# Precision_Singleboard_Charlieplex.net
KiCad netlist of a schematic drawn in EAGLE
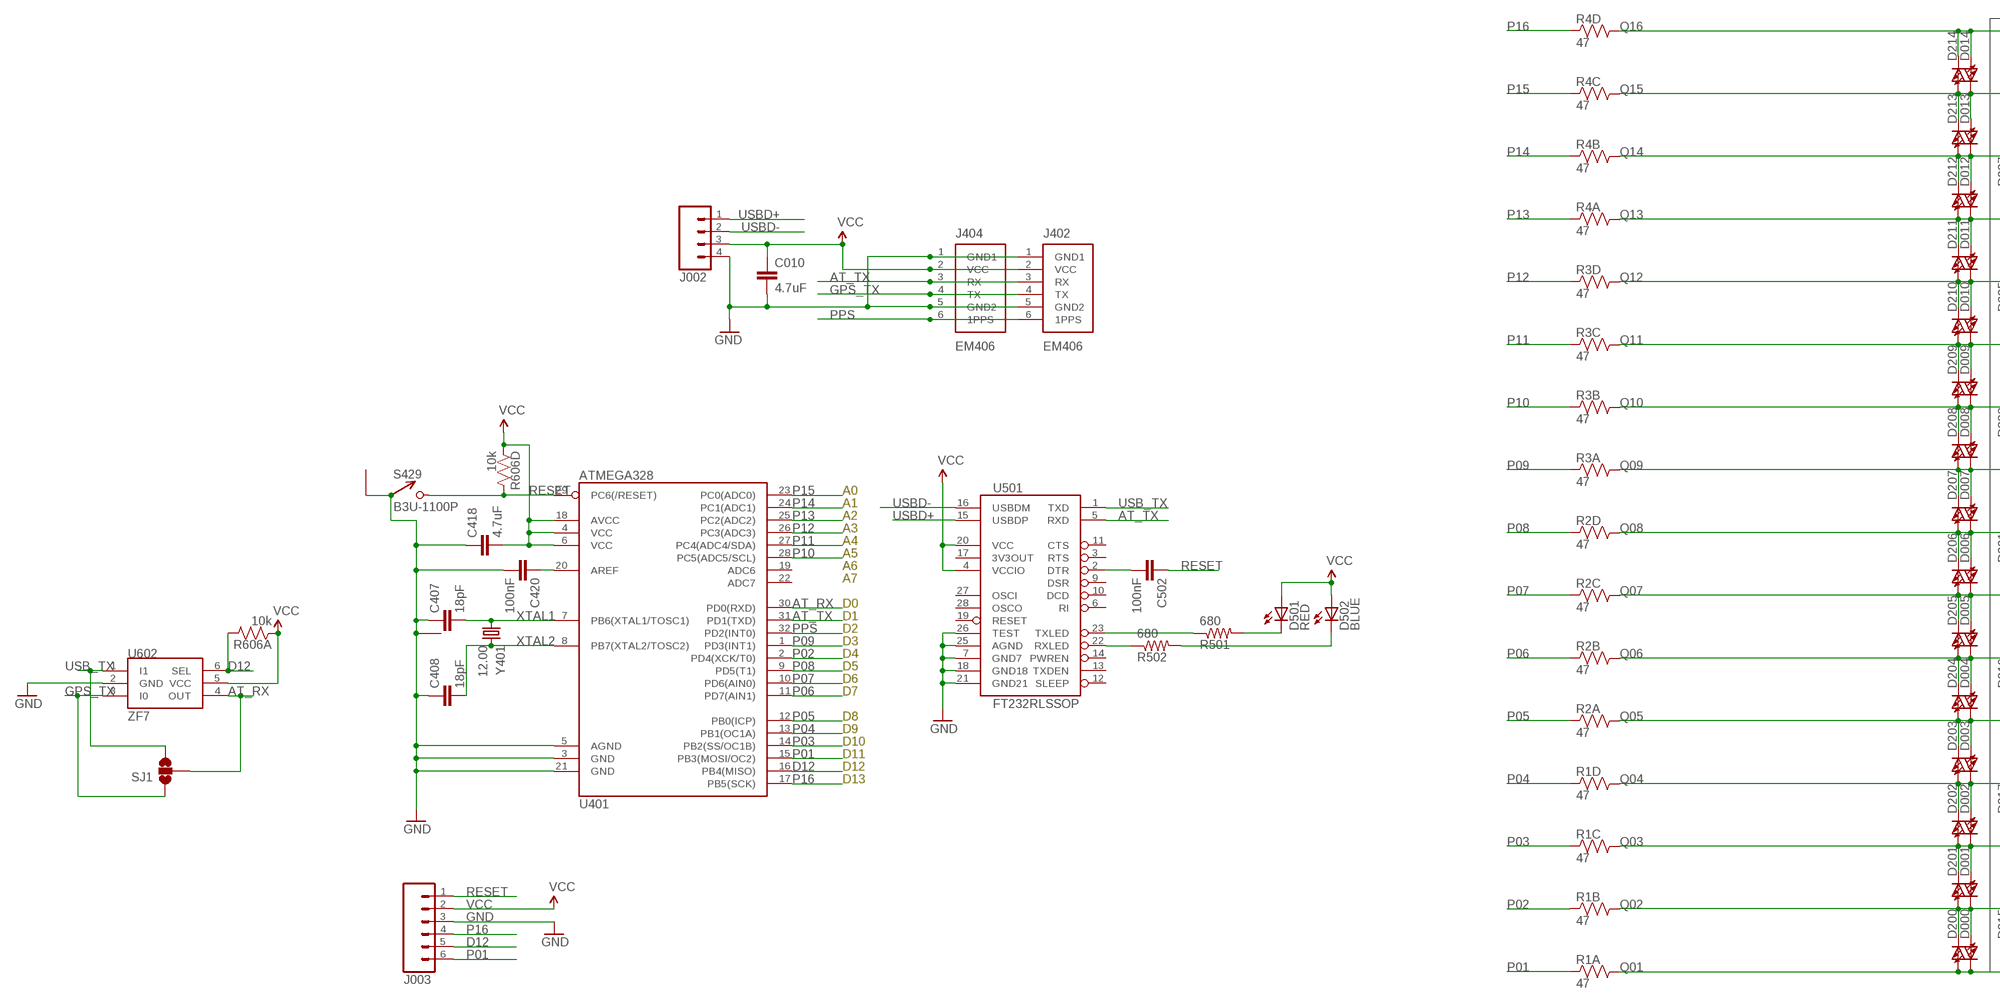
[diagram p0: schematic, sheet 1, part 1 of 2]
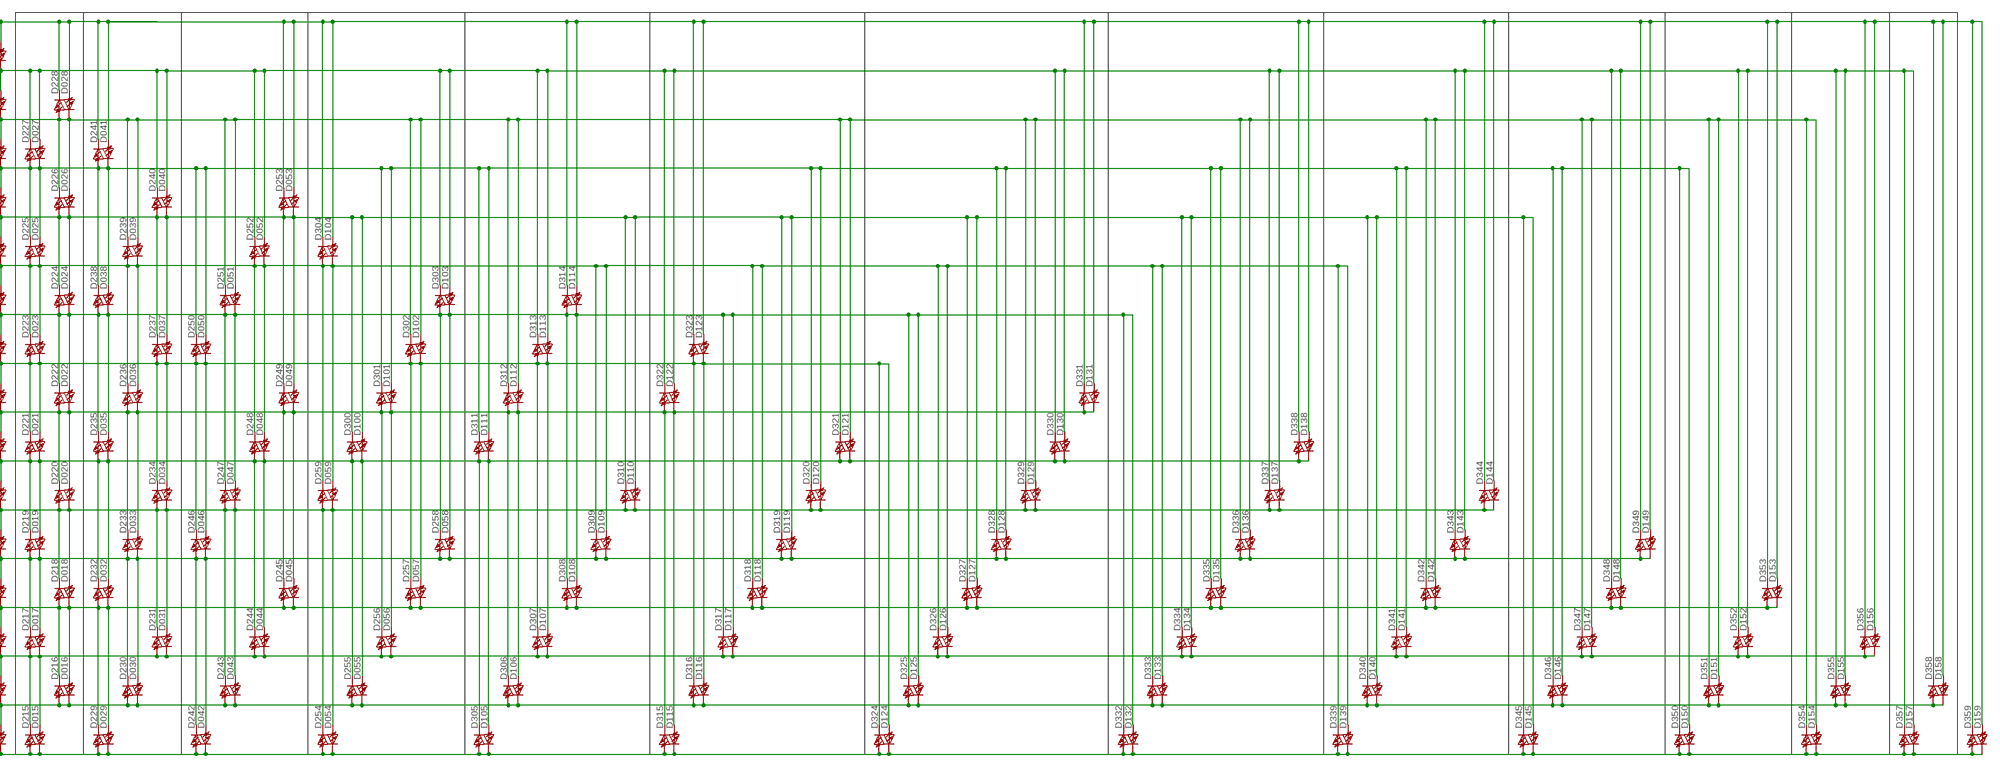
[diagram p1: schematic, sheet 1, part 2 of 2]

(export (version "E")
  (design (tool "Eeschema 10.0.6"))
  (components
    (comp (ref "C010")
      (value "4.7uF")
      (footprint "eagle-import:0603-CAP")
      (libsource (lib "eagle-import") (part "CAP0603-CAP"))
    )
    (comp (ref "C407")
      (value "18pF")
      (footprint "eagle-import:0603-CAP")
      (libsource (lib "eagle-import") (part "CAP0603-CAP"))
    )
    (comp (ref "C408")
      (value "18pF")
      (footprint "eagle-import:0603-CAP")
      (libsource (lib "eagle-import") (part "CAP0603-CAP"))
    )
    (comp (ref "C418")
      (value "4.7uF")
      (footprint "eagle-import:0603-CAP")
      (libsource (lib "eagle-import") (part "CAP0603-CAP"))
    )
    (comp (ref "C420")
      (value "100nF")
      (footprint "eagle-import:0603-CAP")
      (libsource (lib "eagle-import") (part "CAP0603-CAP"))
    )
    (comp (ref "C502")
      (value "100nF")
      (footprint "eagle-import:0603-CAP")
      (libsource (lib "eagle-import") (part "CAP0603-CAP"))
    )
    (comp (ref "D000")
      (value "HOUR")
      (footprint "eagle-import:LED-0603")
      (libsource (lib "eagle-import") (part "LED0603"))
    )
    (comp (ref "D001")
      (value "HOUR")
      (footprint "eagle-import:LED-0603")
      (libsource (lib "eagle-import") (part "LED0603"))
    )
    (comp (ref "D002")
      (value "HOUR")
      (footprint "eagle-import:LED-0603")
      (libsource (lib "eagle-import") (part "LED0603"))
    )
    (comp (ref "D003")
      (value "HOUR")
      (footprint "eagle-import:LED-0603")
      (libsource (lib "eagle-import") (part "LED0603"))
    )
    (comp (ref "D004")
      (value "HOUR")
      (footprint "eagle-import:LED-0603")
      (libsource (lib "eagle-import") (part "LED0603"))
    )
    (comp (ref "D005")
      (value "HOUR")
      (footprint "eagle-import:LED-0603")
      (libsource (lib "eagle-import") (part "LED0603"))
    )
    (comp (ref "D006")
      (value "HOUR")
      (footprint "eagle-import:LED-0603")
      (libsource (lib "eagle-import") (part "LED0603"))
    )
    (comp (ref "D007")
      (value "HOUR")
      (footprint "eagle-import:LED-0603")
      (libsource (lib "eagle-import") (part "LED0603"))
    )
    (comp (ref "D008")
      (value "HOUR")
      (footprint "eagle-import:LED-0603")
      (libsource (lib "eagle-import") (part "LED0603"))
    )
    (comp (ref "D009")
      (value "HOUR")
      (footprint "eagle-import:LED-0603")
      (libsource (lib "eagle-import") (part "LED0603"))
    )
    (comp (ref "D010")
      (value "HOUR")
      (footprint "eagle-import:LED-0603")
      (libsource (lib "eagle-import") (part "LED0603"))
    )
    (comp (ref "D011")
      (value "HOUR")
      (footprint "eagle-import:LED-0603")
      (libsource (lib "eagle-import") (part "LED0603"))
    )
    (comp (ref "D012")
      (value "HOUR")
      (footprint "eagle-import:LED-0603")
      (libsource (lib "eagle-import") (part "LED0603"))
    )
    (comp (ref "D013")
      (value "HOUR")
      (footprint "eagle-import:LED-0603")
      (libsource (lib "eagle-import") (part "LED0603"))
    )
    (comp (ref "D014")
      (value "HOUR")
      (footprint "eagle-import:LED-0603")
      (libsource (lib "eagle-import") (part "LED0603"))
    )
    (comp (ref "D015")
      (value "HOUR")
      (footprint "eagle-import:LED-0603")
      (libsource (lib "eagle-import") (part "LED0603"))
    )
    (comp (ref "D016")
      (value "HOUR")
      (footprint "eagle-import:LED-0603")
      (libsource (lib "eagle-import") (part "LED0603"))
    )
    (comp (ref "D017")
      (value "HOUR")
      (footprint "eagle-import:LED-0603")
      (libsource (lib "eagle-import") (part "LED0603"))
    )
    (comp (ref "D018")
      (value "HOUR")
      (footprint "eagle-import:LED-0603")
      (libsource (lib "eagle-import") (part "LED0603"))
    )
    (comp (ref "D019")
      (value "HOUR")
      (footprint "eagle-import:LED-0603")
      (libsource (lib "eagle-import") (part "LED0603"))
    )
    (comp (ref "D020")
      (value "HOUR")
      (footprint "eagle-import:LED-0603")
      (libsource (lib "eagle-import") (part "LED0603"))
    )
    (comp (ref "D021")
      (value "HOUR")
      (footprint "eagle-import:LED-0603")
      (libsource (lib "eagle-import") (part "LED0603"))
    )
    (comp (ref "D022")
      (value "HOUR")
      (footprint "eagle-import:LED-0603")
      (libsource (lib "eagle-import") (part "LED0603"))
    )
    (comp (ref "D023")
      (value "HOUR")
      (footprint "eagle-import:LED-0603")
      (libsource (lib "eagle-import") (part "LED0603"))
    )
    (comp (ref "D024")
      (value "HOUR")
      (footprint "eagle-import:LED-0603")
      (libsource (lib "eagle-import") (part "LED0603"))
    )
    (comp (ref "D025")
      (value "HOUR")
      (footprint "eagle-import:LED-0603")
      (libsource (lib "eagle-import") (part "LED0603"))
    )
    (comp (ref "D026")
      (value "HOUR")
      (footprint "eagle-import:LED-0603")
      (libsource (lib "eagle-import") (part "LED0603"))
    )
    (comp (ref "D027")
      (value "HOUR")
      (footprint "eagle-import:LED-0603")
      (libsource (lib "eagle-import") (part "LED0603"))
    )
    (comp (ref "D028")
      (value "HOUR")
      (footprint "eagle-import:LED-0603")
      (libsource (lib "eagle-import") (part "LED0603"))
    )
    (comp (ref "D029")
      (value "HOUR")
      (footprint "eagle-import:LED-0603")
      (libsource (lib "eagle-import") (part "LED0603"))
    )
    (comp (ref "D030")
      (value "HOUR")
      (footprint "eagle-import:LED-0603")
      (libsource (lib "eagle-import") (part "LED0603"))
    )
    (comp (ref "D031")
      (value "HOUR")
      (footprint "eagle-import:LED-0603")
      (libsource (lib "eagle-import") (part "LED0603"))
    )
    (comp (ref "D032")
      (value "HOUR")
      (footprint "eagle-import:LED-0603")
      (libsource (lib "eagle-import") (part "LED0603"))
    )
    (comp (ref "D033")
      (value "HOUR")
      (footprint "eagle-import:LED-0603")
      (libsource (lib "eagle-import") (part "LED0603"))
    )
    (comp (ref "D034")
      (value "HOUR")
      (footprint "eagle-import:LED-0603")
      (libsource (lib "eagle-import") (part "LED0603"))
    )
    (comp (ref "D035")
      (value "HOUR")
      (footprint "eagle-import:LED-0603")
      (libsource (lib "eagle-import") (part "LED0603"))
    )
    (comp (ref "D036")
      (value "HOUR")
      (footprint "eagle-import:LED-0603")
      (libsource (lib "eagle-import") (part "LED0603"))
    )
    (comp (ref "D037")
      (value "HOUR")
      (footprint "eagle-import:LED-0603")
      (libsource (lib "eagle-import") (part "LED0603"))
    )
    (comp (ref "D038")
      (value "HOUR")
      (footprint "eagle-import:LED-0603")
      (libsource (lib "eagle-import") (part "LED0603"))
    )
    (comp (ref "D039")
      (value "HOUR")
      (footprint "eagle-import:LED-0603")
      (libsource (lib "eagle-import") (part "LED0603"))
    )
    (comp (ref "D040")
      (value "HOUR")
      (footprint "eagle-import:LED-0603")
      (libsource (lib "eagle-import") (part "LED0603"))
    )
    (comp (ref "D041")
      (value "HOUR")
      (footprint "eagle-import:LED-0603")
      (libsource (lib "eagle-import") (part "LED0603"))
    )
    (comp (ref "D042")
      (value "HOUR")
      (footprint "eagle-import:LED-0603")
      (libsource (lib "eagle-import") (part "LED0603"))
    )
    (comp (ref "D043")
      (value "HOUR")
      (footprint "eagle-import:LED-0603")
      (libsource (lib "eagle-import") (part "LED0603"))
    )
    (comp (ref "D044")
      (value "HOUR")
      (footprint "eagle-import:LED-0603")
      (libsource (lib "eagle-import") (part "LED0603"))
    )
    (comp (ref "D045")
      (value "HOUR")
      (footprint "eagle-import:LED-0603")
      (libsource (lib "eagle-import") (part "LED0603"))
    )
    (comp (ref "D046")
      (value "HOUR")
      (footprint "eagle-import:LED-0603")
      (libsource (lib "eagle-import") (part "LED0603"))
    )
    (comp (ref "D047")
      (value "HOUR")
      (footprint "eagle-import:LED-0603")
      (libsource (lib "eagle-import") (part "LED0603"))
    )
    (comp (ref "D048")
      (value "HOUR")
      (footprint "eagle-import:LED-0603")
      (libsource (lib "eagle-import") (part "LED0603"))
    )
    (comp (ref "D049")
      (value "HOUR")
      (footprint "eagle-import:LED-0603")
      (libsource (lib "eagle-import") (part "LED0603"))
    )
    (comp (ref "D050")
      (value "HOUR")
      (footprint "eagle-import:LED-0603")
      (libsource (lib "eagle-import") (part "LED0603"))
    )
    (comp (ref "D051")
      (value "HOUR")
      (footprint "eagle-import:LED-0603")
      (libsource (lib "eagle-import") (part "LED0603"))
    )
    (comp (ref "D052")
      (value "HOUR")
      (footprint "eagle-import:LED-0603")
      (libsource (lib "eagle-import") (part "LED0603"))
    )
    (comp (ref "D053")
      (value "HOUR")
      (footprint "eagle-import:LED-0603")
      (libsource (lib "eagle-import") (part "LED0603"))
    )
    (comp (ref "D054")
      (value "HOUR")
      (footprint "eagle-import:LED-0603")
      (libsource (lib "eagle-import") (part "LED0603"))
    )
    (comp (ref "D055")
      (value "HOUR")
      (footprint "eagle-import:LED-0603")
      (libsource (lib "eagle-import") (part "LED0603"))
    )
    (comp (ref "D056")
      (value "HOUR")
      (footprint "eagle-import:LED-0603")
      (libsource (lib "eagle-import") (part "LED0603"))
    )
    (comp (ref "D057")
      (value "HOUR")
      (footprint "eagle-import:LED-0603")
      (libsource (lib "eagle-import") (part "LED0603"))
    )
    (comp (ref "D058")
      (value "HOUR")
      (footprint "eagle-import:LED-0603")
      (libsource (lib "eagle-import") (part "LED0603"))
    )
    (comp (ref "D059")
      (value "HOUR")
      (footprint "eagle-import:LED-0603")
      (libsource (lib "eagle-import") (part "LED0603"))
    )
    (comp (ref "D100")
      (value "HOUR")
      (footprint "eagle-import:LED-0603")
      (libsource (lib "eagle-import") (part "LED0603"))
    )
    (comp (ref "D101")
      (value "HOUR")
      (footprint "eagle-import:LED-0603")
      (libsource (lib "eagle-import") (part "LED0603"))
    )
    (comp (ref "D102")
      (value "HOUR")
      (footprint "eagle-import:LED-0603")
      (libsource (lib "eagle-import") (part "LED0603"))
    )
    (comp (ref "D103")
      (value "HOUR")
      (footprint "eagle-import:LED-0603")
      (libsource (lib "eagle-import") (part "LED0603"))
    )
    (comp (ref "D104")
      (value "HOUR")
      (footprint "eagle-import:LED-0603")
      (libsource (lib "eagle-import") (part "LED0603"))
    )
    (comp (ref "D105")
      (value "HOUR")
      (footprint "eagle-import:LED-0603")
      (libsource (lib "eagle-import") (part "LED0603"))
    )
    (comp (ref "D106")
      (value "HOUR")
      (footprint "eagle-import:LED-0603")
      (libsource (lib "eagle-import") (part "LED0603"))
    )
    (comp (ref "D107")
      (value "HOUR")
      (footprint "eagle-import:LED-0603")
      (libsource (lib "eagle-import") (part "LED0603"))
    )
    (comp (ref "D108")
      (value "HOUR")
      (footprint "eagle-import:LED-0603")
      (libsource (lib "eagle-import") (part "LED0603"))
    )
    (comp (ref "D109")
      (value "HOUR")
      (footprint "eagle-import:LED-0603")
      (libsource (lib "eagle-import") (part "LED0603"))
    )
    (comp (ref "D110")
      (value "HOUR")
      (footprint "eagle-import:LED-0603")
      (libsource (lib "eagle-import") (part "LED0603"))
    )
    (comp (ref "D111")
      (value "HOUR")
      (footprint "eagle-import:LED-0603")
      (libsource (lib "eagle-import") (part "LED0603"))
    )
    (comp (ref "D112")
      (value "HOUR")
      (footprint "eagle-import:LED-0603")
      (libsource (lib "eagle-import") (part "LED0603"))
    )
    (comp (ref "D113")
      (value "HOUR")
      (footprint "eagle-import:LED-0603")
      (libsource (lib "eagle-import") (part "LED0603"))
    )
    (comp (ref "D114")
      (value "HOUR")
      (footprint "eagle-import:LED-0603")
      (libsource (lib "eagle-import") (part "LED0603"))
    )
    (comp (ref "D115")
      (value "HOUR")
      (footprint "eagle-import:LED-0603")
      (libsource (lib "eagle-import") (part "LED0603"))
    )
    (comp (ref "D116")
      (value "HOUR")
      (footprint "eagle-import:LED-0603")
      (libsource (lib "eagle-import") (part "LED0603"))
    )
    (comp (ref "D117")
      (value "HOUR")
      (footprint "eagle-import:LED-0603")
      (libsource (lib "eagle-import") (part "LED0603"))
    )
    (comp (ref "D118")
      (value "HOUR")
      (footprint "eagle-import:LED-0603")
      (libsource (lib "eagle-import") (part "LED0603"))
    )
    (comp (ref "D119")
      (value "HOUR")
      (footprint "eagle-import:LED-0603")
      (libsource (lib "eagle-import") (part "LED0603"))
    )
    (comp (ref "D120")
      (value "HOUR")
      (footprint "eagle-import:LED-0603")
      (libsource (lib "eagle-import") (part "LED0603"))
    )
    (comp (ref "D121")
      (value "HOUR")
      (footprint "eagle-import:LED-0603")
      (libsource (lib "eagle-import") (part "LED0603"))
    )
    (comp (ref "D122")
      (value "HOUR")
      (footprint "eagle-import:LED-0603")
      (libsource (lib "eagle-import") (part "LED0603"))
    )
    (comp (ref "D123")
      (value "HOUR")
      (footprint "eagle-import:LED-0603")
      (libsource (lib "eagle-import") (part "LED0603"))
    )
    (comp (ref "D124")
      (value "HOUR")
      (footprint "eagle-import:LED-0603")
      (libsource (lib "eagle-import") (part "LED0603"))
    )
    (comp (ref "D125")
      (value "HOUR")
      (footprint "eagle-import:LED-0603")
      (libsource (lib "eagle-import") (part "LED0603"))
    )
    (comp (ref "D126")
      (value "HOUR")
      (footprint "eagle-import:LED-0603")
      (libsource (lib "eagle-import") (part "LED0603"))
    )
    (comp (ref "D127")
      (value "HOUR")
      (footprint "eagle-import:LED-0603")
      (libsource (lib "eagle-import") (part "LED0603"))
    )
    (comp (ref "D128")
      (value "HOUR")
      (footprint "eagle-import:LED-0603")
      (libsource (lib "eagle-import") (part "LED0603"))
    )
    (comp (ref "D129")
      (value "HOUR")
      (footprint "eagle-import:LED-0603")
      (libsource (lib "eagle-import") (part "LED0603"))
    )
    (comp (ref "D130")
      (value "HOUR")
      (footprint "eagle-import:LED-0603")
      (libsource (lib "eagle-import") (part "LED0603"))
    )
    (comp (ref "D131")
      (value "HOUR")
      (footprint "eagle-import:LED-0603")
      (libsource (lib "eagle-import") (part "LED0603"))
    )
    (comp (ref "D132")
      (value "HOUR")
      (footprint "eagle-import:LED-0603")
      (libsource (lib "eagle-import") (part "LED0603"))
    )
    (comp (ref "D133")
      (value "HOUR")
      (footprint "eagle-import:LED-0603")
      (libsource (lib "eagle-import") (part "LED0603"))
    )
    (comp (ref "D134")
      (value "HOUR")
      (footprint "eagle-import:LED-0603")
      (libsource (lib "eagle-import") (part "LED0603"))
    )
    (comp (ref "D135")
      (value "HOUR")
      (footprint "eagle-import:LED-0603")
      (libsource (lib "eagle-import") (part "LED0603"))
    )
    (comp (ref "D136")
      (value "HOUR")
      (footprint "eagle-import:LED-0603")
      (libsource (lib "eagle-import") (part "LED0603"))
    )
    (comp (ref "D137")
      (value "HOUR")
      (footprint "eagle-import:LED-0603")
      (libsource (lib "eagle-import") (part "LED0603"))
    )
    (comp (ref "D138")
      (value "HOUR")
      (footprint "eagle-import:LED-0603")
      (libsource (lib "eagle-import") (part "LED0603"))
    )
    (comp (ref "D139")
      (value "HOUR")
      (footprint "eagle-import:LED-0603")
      (libsource (lib "eagle-import") (part "LED0603"))
    )
    (comp (ref "D140")
      (value "HOUR")
      (footprint "eagle-import:LED-0603")
      (libsource (lib "eagle-import") (part "LED0603"))
    )
    (comp (ref "D141")
      (value "HOUR")
      (footprint "eagle-import:LED-0603")
      (libsource (lib "eagle-import") (part "LED0603"))
    )
    (comp (ref "D142")
      (value "HOUR")
      (footprint "eagle-import:LED-0603")
      (libsource (lib "eagle-import") (part "LED0603"))
    )
    (comp (ref "D143")
      (value "HOUR")
      (footprint "eagle-import:LED-0603")
      (libsource (lib "eagle-import") (part "LED0603"))
    )
    (comp (ref "D144")
      (value "HOUR")
      (footprint "eagle-import:LED-0603")
      (libsource (lib "eagle-import") (part "LED0603"))
    )
    (comp (ref "D145")
      (value "HOUR")
      (footprint "eagle-import:LED-0603")
      (libsource (lib "eagle-import") (part "LED0603"))
    )
    (comp (ref "D146")
      (value "HOUR")
      (footprint "eagle-import:LED-0603")
      (libsource (lib "eagle-import") (part "LED0603"))
    )
    (comp (ref "D147")
      (value "HOUR")
      (footprint "eagle-import:LED-0603")
      (libsource (lib "eagle-import") (part "LED0603"))
    )
    (comp (ref "D148")
      (value "HOUR")
      (footprint "eagle-import:LED-0603")
      (libsource (lib "eagle-import") (part "LED0603"))
    )
    (comp (ref "D149")
      (value "HOUR")
      (footprint "eagle-import:LED-0603")
      (libsource (lib "eagle-import") (part "LED0603"))
    )
    (comp (ref "D150")
      (value "HOUR")
      (footprint "eagle-import:LED-0603")
      (libsource (lib "eagle-import") (part "LED0603"))
    )
    (comp (ref "D151")
      (value "HOUR")
      (footprint "eagle-import:LED-0603")
      (libsource (lib "eagle-import") (part "LED0603"))
    )
    (comp (ref "D152")
      (value "HOUR")
      (footprint "eagle-import:LED-0603")
      (libsource (lib "eagle-import") (part "LED0603"))
    )
    (comp (ref "D153")
      (value "HOUR")
      (footprint "eagle-import:LED-0603")
      (libsource (lib "eagle-import") (part "LED0603"))
    )
    (comp (ref "D154")
      (value "HOUR")
      (footprint "eagle-import:LED-0603")
      (libsource (lib "eagle-import") (part "LED0603"))
    )
    (comp (ref "D155")
      (value "HOUR")
      (footprint "eagle-import:LED-0603")
      (libsource (lib "eagle-import") (part "LED0603"))
    )
    (comp (ref "D156")
      (value "HOUR")
      (footprint "eagle-import:LED-0603")
      (libsource (lib "eagle-import") (part "LED0603"))
    )
    (comp (ref "D157")
      (value "HOUR")
      (footprint "eagle-import:LED-0603")
      (libsource (lib "eagle-import") (part "LED0603"))
    )
    (comp (ref "D158")
      (value "HOUR")
      (footprint "eagle-import:LED-0603")
      (libsource (lib "eagle-import") (part "LED0603"))
    )
    (comp (ref "D159")
      (value "HOUR")
      (footprint "eagle-import:LED-0603")
      (libsource (lib "eagle-import") (part "LED0603"))
    )
    (comp (ref "D200")
      (value "HOUR")
      (footprint "eagle-import:LED-0603")
      (libsource (lib "eagle-import") (part "LED0603"))
    )
    (comp (ref "D201")
      (value "HOUR")
      (footprint "eagle-import:LED-0603")
      (libsource (lib "eagle-import") (part "LED0603"))
    )
    (comp (ref "D202")
      (value "HOUR")
      (footprint "eagle-import:LED-0603")
      (libsource (lib "eagle-import") (part "LED0603"))
    )
    (comp (ref "D203")
      (value "HOUR")
      (footprint "eagle-import:LED-0603")
      (libsource (lib "eagle-import") (part "LED0603"))
    )
    (comp (ref "D204")
      (value "HOUR")
      (footprint "eagle-import:LED-0603")
      (libsource (lib "eagle-import") (part "LED0603"))
    )
    (comp (ref "D205")
      (value "HOUR")
      (footprint "eagle-import:LED-0603")
      (libsource (lib "eagle-import") (part "LED0603"))
    )
    (comp (ref "D206")
      (value "HOUR")
      (footprint "eagle-import:LED-0603")
      (libsource (lib "eagle-import") (part "LED0603"))
    )
    (comp (ref "D207")
      (value "HOUR")
      (footprint "eagle-import:LED-0603")
      (libsource (lib "eagle-import") (part "LED0603"))
    )
    (comp (ref "D208")
      (value "HOUR")
      (footprint "eagle-import:LED-0603")
      (libsource (lib "eagle-import") (part "LED0603"))
    )
    (comp (ref "D209")
      (value "HOUR")
      (footprint "eagle-import:LED-0603")
      (libsource (lib "eagle-import") (part "LED0603"))
    )
    (comp (ref "D210")
      (value "HOUR")
      (footprint "eagle-import:LED-0603")
      (libsource (lib "eagle-import") (part "LED0603"))
    )
    (comp (ref "D211")
      (value "HOUR")
      (footprint "eagle-import:LED-0603")
      (libsource (lib "eagle-import") (part "LED0603"))
    )
    (comp (ref "D212")
      (value "HOUR")
      (footprint "eagle-import:LED-0603")
      (libsource (lib "eagle-import") (part "LED0603"))
    )
    (comp (ref "D213")
      (value "HOUR")
      (footprint "eagle-import:LED-0603")
      (libsource (lib "eagle-import") (part "LED0603"))
    )
    (comp (ref "D214")
      (value "HOUR")
      (footprint "eagle-import:LED-0603")
      (libsource (lib "eagle-import") (part "LED0603"))
    )
    (comp (ref "D215")
      (value "HOUR")
      (footprint "eagle-import:LED-0603")
      (libsource (lib "eagle-import") (part "LED0603"))
    )
    (comp (ref "D216")
      (value "HOUR")
      (footprint "eagle-import:LED-0603")
      (libsource (lib "eagle-import") (part "LED0603"))
    )
    (comp (ref "D217")
      (value "HOUR")
      (footprint "eagle-import:LED-0603")
      (libsource (lib "eagle-import") (part "LED0603"))
    )
    (comp (ref "D218")
      (value "HOUR")
      (footprint "eagle-import:LED-0603")
      (libsource (lib "eagle-import") (part "LED0603"))
    )
    (comp (ref "D219")
      (value "HOUR")
      (footprint "eagle-import:LED-0603")
      (libsource (lib "eagle-import") (part "LED0603"))
    )
    (comp (ref "D220")
      (value "HOUR")
      (footprint "eagle-import:LED-0603")
      (libsource (lib "eagle-import") (part "LED0603"))
    )
    (comp (ref "D221")
      (value "HOUR")
      (footprint "eagle-import:LED-0603")
      (libsource (lib "eagle-import") (part "LED0603"))
    )
    (comp (ref "D222")
      (value "HOUR")
      (footprint "eagle-import:LED-0603")
      (libsource (lib "eagle-import") (part "LED0603"))
    )
    (comp (ref "D223")
      (value "HOUR")
      (footprint "eagle-import:LED-0603")
      (libsource (lib "eagle-import") (part "LED0603"))
    )
    (comp (ref "D224")
      (value "HOUR")
      (footprint "eagle-import:LED-0603")
      (libsource (lib "eagle-import") (part "LED0603"))
    )
    (comp (ref "D225")
      (value "HOUR")
      (footprint "eagle-import:LED-0603")
      (libsource (lib "eagle-import") (part "LED0603"))
    )
    (comp (ref "D226")
      (value "HOUR")
      (footprint "eagle-import:LED-0603")
      (libsource (lib "eagle-import") (part "LED0603"))
    )
    (comp (ref "D227")
      (value "HOUR")
      (footprint "eagle-import:LED-0603")
      (libsource (lib "eagle-import") (part "LED0603"))
    )
    (comp (ref "D228")
      (value "HOUR")
      (footprint "eagle-import:LED-0603")
      (libsource (lib "eagle-import") (part "LED0603"))
    )
    (comp (ref "D229")
      (value "HOUR")
      (footprint "eagle-import:LED-0603")
      (libsource (lib "eagle-import") (part "LED0603"))
    )
    (comp (ref "D230")
      (value "HOUR")
      (footprint "eagle-import:LED-0603")
      (libsource (lib "eagle-import") (part "LED0603"))
    )
    (comp (ref "D231")
      (value "HOUR")
      (footprint "eagle-import:LED-0603")
      (libsource (lib "eagle-import") (part "LED0603"))
    )
    (comp (ref "D232")
      (value "HOUR")
      (footprint "eagle-import:LED-0603")
      (libsource (lib "eagle-import") (part "LED0603"))
    )
    (comp (ref "D233")
      (value "HOUR")
      (footprint "eagle-import:LED-0603")
      (libsource (lib "eagle-import") (part "LED0603"))
    )
    (comp (ref "D234")
      (value "HOUR")
      (footprint "eagle-import:LED-0603")
      (libsource (lib "eagle-import") (part "LED0603"))
    )
    (comp (ref "D235")
      (value "HOUR")
      (footprint "eagle-import:LED-0603")
      (libsource (lib "eagle-import") (part "LED0603"))
    )
    (comp (ref "D236")
      (value "HOUR")
      (footprint "eagle-import:LED-0603")
      (libsource (lib "eagle-import") (part "LED0603"))
    )
    (comp (ref "D237")
      (value "HOUR")
      (footprint "eagle-import:LED-0603")
      (libsource (lib "eagle-import") (part "LED0603"))
    )
    (comp (ref "D238")
      (value "HOUR")
      (footprint "eagle-import:LED-0603")
      (libsource (lib "eagle-import") (part "LED0603"))
    )
    (comp (ref "D239")
      (value "HOUR")
      (footprint "eagle-import:LED-0603")
      (libsource (lib "eagle-import") (part "LED0603"))
    )
    (comp (ref "D240")
      (value "HOUR")
      (footprint "eagle-import:LED-0603")
      (libsource (lib "eagle-import") (part "LED0603"))
    )
    (comp (ref "D241")
      (value "HOUR")
      (footprint "eagle-import:LED-0603")
      (libsource (lib "eagle-import") (part "LED0603"))
    )
    (comp (ref "D242")
      (value "HOUR")
      (footprint "eagle-import:LED-0603")
      (libsource (lib "eagle-import") (part "LED0603"))
    )
    (comp (ref "D243")
      (value "HOUR")
      (footprint "eagle-import:LED-0603")
      (libsource (lib "eagle-import") (part "LED0603"))
    )
    (comp (ref "D244")
      (value "HOUR")
      (footprint "eagle-import:LED-0603")
      (libsource (lib "eagle-import") (part "LED0603"))
    )
    (comp (ref "D245")
      (value "HOUR")
      (footprint "eagle-import:LED-0603")
      (libsource (lib "eagle-import") (part "LED0603"))
    )
    (comp (ref "D246")
      (value "HOUR")
      (footprint "eagle-import:LED-0603")
      (libsource (lib "eagle-import") (part "LED0603"))
    )
    (comp (ref "D247")
      (value "HOUR")
      (footprint "eagle-import:LED-0603")
      (libsource (lib "eagle-import") (part "LED0603"))
    )
    (comp (ref "D248")
      (value "HOUR")
      (footprint "eagle-import:LED-0603")
      (libsource (lib "eagle-import") (part "LED0603"))
    )
    (comp (ref "D249")
      (value "HOUR")
      (footprint "eagle-import:LED-0603")
      (libsource (lib "eagle-import") (part "LED0603"))
    )
    (comp (ref "D250")
      (value "HOUR")
      (footprint "eagle-import:LED-0603")
      (libsource (lib "eagle-import") (part "LED0603"))
    )
    (comp (ref "D251")
      (value "HOUR")
      (footprint "eagle-import:LED-0603")
      (libsource (lib "eagle-import") (part "LED0603"))
    )
    (comp (ref "D252")
      (value "HOUR")
      (footprint "eagle-import:LED-0603")
      (libsource (lib "eagle-import") (part "LED0603"))
    )
    (comp (ref "D253")
      (value "HOUR")
      (footprint "eagle-import:LED-0603")
      (libsource (lib "eagle-import") (part "LED0603"))
    )
    (comp (ref "D254")
      (value "HOUR")
      (footprint "eagle-import:LED-0603")
      (libsource (lib "eagle-import") (part "LED0603"))
    )
    (comp (ref "D255")
      (value "HOUR")
      (footprint "eagle-import:LED-0603")
      (libsource (lib "eagle-import") (part "LED0603"))
    )
    (comp (ref "D256")
      (value "HOUR")
      (footprint "eagle-import:LED-0603")
      (libsource (lib "eagle-import") (part "LED0603"))
    )
    (comp (ref "D257")
      (value "HOUR")
      (footprint "eagle-import:LED-0603")
      (libsource (lib "eagle-import") (part "LED0603"))
    )
    (comp (ref "D258")
      (value "HOUR")
      (footprint "eagle-import:LED-0603")
      (libsource (lib "eagle-import") (part "LED0603"))
    )
    (comp (ref "D259")
      (value "HOUR")
      (footprint "eagle-import:LED-0603")
      (libsource (lib "eagle-import") (part "LED0603"))
    )
    (comp (ref "D300")
      (value "HOUR")
      (footprint "eagle-import:LED-0603")
      (libsource (lib "eagle-import") (part "LED0603"))
    )
    (comp (ref "D301")
      (value "HOUR")
      (footprint "eagle-import:LED-0603")
      (libsource (lib "eagle-import") (part "LED0603"))
    )
    (comp (ref "D302")
      (value "HOUR")
      (footprint "eagle-import:LED-0603")
      (libsource (lib "eagle-import") (part "LED0603"))
    )
    (comp (ref "D303")
      (value "HOUR")
      (footprint "eagle-import:LED-0603")
      (libsource (lib "eagle-import") (part "LED0603"))
    )
    (comp (ref "D304")
      (value "HOUR")
      (footprint "eagle-import:LED-0603")
      (libsource (lib "eagle-import") (part "LED0603"))
    )
    (comp (ref "D305")
      (value "HOUR")
      (footprint "eagle-import:LED-0603")
      (libsource (lib "eagle-import") (part "LED0603"))
    )
    (comp (ref "D306")
      (value "HOUR")
      (footprint "eagle-import:LED-0603")
      (libsource (lib "eagle-import") (part "LED0603"))
    )
    (comp (ref "D307")
      (value "HOUR")
      (footprint "eagle-import:LED-0603")
      (libsource (lib "eagle-import") (part "LED0603"))
    )
    (comp (ref "D308")
      (value "HOUR")
      (footprint "eagle-import:LED-0603")
      (libsource (lib "eagle-import") (part "LED0603"))
    )
    (comp (ref "D309")
      (value "HOUR")
      (footprint "eagle-import:LED-0603")
      (libsource (lib "eagle-import") (part "LED0603"))
    )
    (comp (ref "D310")
      (value "HOUR")
      (footprint "eagle-import:LED-0603")
      (libsource (lib "eagle-import") (part "LED0603"))
    )
    (comp (ref "D311")
      (value "HOUR")
      (footprint "eagle-import:LED-0603")
      (libsource (lib "eagle-import") (part "LED0603"))
    )
    (comp (ref "D312")
      (value "HOUR")
      (footprint "eagle-import:LED-0603")
      (libsource (lib "eagle-import") (part "LED0603"))
    )
    (comp (ref "D313")
      (value "HOUR")
      (footprint "eagle-import:LED-0603")
      (libsource (lib "eagle-import") (part "LED0603"))
    )
    (comp (ref "D314")
      (value "HOUR")
      (footprint "eagle-import:LED-0603")
      (libsource (lib "eagle-import") (part "LED0603"))
    )
    (comp (ref "D315")
      (value "HOUR")
      (footprint "eagle-import:LED-0603")
      (libsource (lib "eagle-import") (part "LED0603"))
    )
    (comp (ref "D316")
      (value "HOUR")
      (footprint "eagle-import:LED-0603")
      (libsource (lib "eagle-import") (part "LED0603"))
    )
    (comp (ref "D317")
      (value "HOUR")
      (footprint "eagle-import:LED-0603")
      (libsource (lib "eagle-import") (part "LED0603"))
    )
    (comp (ref "D318")
      (value "HOUR")
      (footprint "eagle-import:LED-0603")
      (libsource (lib "eagle-import") (part "LED0603"))
    )
    (comp (ref "D319")
      (value "HOUR")
      (footprint "eagle-import:LED-0603")
      (libsource (lib "eagle-import") (part "LED0603"))
    )
    (comp (ref "D320")
      (value "HOUR")
      (footprint "eagle-import:LED-0603")
      (libsource (lib "eagle-import") (part "LED0603"))
    )
    (comp (ref "D321")
      (value "HOUR")
      (footprint "eagle-import:LED-0603")
      (libsource (lib "eagle-import") (part "LED0603"))
    )
    (comp (ref "D322")
      (value "HOUR")
      (footprint "eagle-import:LED-0603")
      (libsource (lib "eagle-import") (part "LED0603"))
    )
    (comp (ref "D323")
      (value "HOUR")
      (footprint "eagle-import:LED-0603")
      (libsource (lib "eagle-import") (part "LED0603"))
    )
    (comp (ref "D324")
      (value "HOUR")
      (footprint "eagle-import:LED-0603")
      (libsource (lib "eagle-import") (part "LED0603"))
    )
    (comp (ref "D325")
      (value "HOUR")
      (footprint "eagle-import:LED-0603")
      (libsource (lib "eagle-import") (part "LED0603"))
    )
    (comp (ref "D326")
      (value "HOUR")
      (footprint "eagle-import:LED-0603")
      (libsource (lib "eagle-import") (part "LED0603"))
    )
    (comp (ref "D327")
      (value "HOUR")
      (footprint "eagle-import:LED-0603")
      (libsource (lib "eagle-import") (part "LED0603"))
    )
    (comp (ref "D328")
      (value "HOUR")
      (footprint "eagle-import:LED-0603")
      (libsource (lib "eagle-import") (part "LED0603"))
    )
    (comp (ref "D329")
      (value "HOUR")
      (footprint "eagle-import:LED-0603")
      (libsource (lib "eagle-import") (part "LED0603"))
    )
    (comp (ref "D330")
      (value "HOUR")
      (footprint "eagle-import:LED-0603")
      (libsource (lib "eagle-import") (part "LED0603"))
    )
    (comp (ref "D331")
      (value "HOUR")
      (footprint "eagle-import:LED-0603")
      (libsource (lib "eagle-import") (part "LED0603"))
    )
    (comp (ref "D332")
      (value "HOUR")
      (footprint "eagle-import:LED-0603")
      (libsource (lib "eagle-import") (part "LED0603"))
    )
    (comp (ref "D333")
      (value "HOUR")
      (footprint "eagle-import:LED-0603")
      (libsource (lib "eagle-import") (part "LED0603"))
    )
    (comp (ref "D334")
      (value "HOUR")
      (footprint "eagle-import:LED-0603")
      (libsource (lib "eagle-import") (part "LED0603"))
    )
    (comp (ref "D335")
      (value "HOUR")
      (footprint "eagle-import:LED-0603")
      (libsource (lib "eagle-import") (part "LED0603"))
    )
    (comp (ref "D336")
      (value "HOUR")
      (footprint "eagle-import:LED-0603")
      (libsource (lib "eagle-import") (part "LED0603"))
    )
    (comp (ref "D337")
      (value "HOUR")
      (footprint "eagle-import:LED-0603")
      (libsource (lib "eagle-import") (part "LED0603"))
    )
    (comp (ref "D338")
      (value "HOUR")
      (footprint "eagle-import:LED-0603")
      (libsource (lib "eagle-import") (part "LED0603"))
    )
    (comp (ref "D339")
      (value "HOUR")
      (footprint "eagle-import:LED-0603")
      (libsource (lib "eagle-import") (part "LED0603"))
    )
    (comp (ref "D340")
      (value "HOUR")
      (footprint "eagle-import:LED-0603")
      (libsource (lib "eagle-import") (part "LED0603"))
    )
    (comp (ref "D341")
      (value "HOUR")
      (footprint "eagle-import:LED-0603")
      (libsource (lib "eagle-import") (part "LED0603"))
    )
    (comp (ref "D342")
      (value "HOUR")
      (footprint "eagle-import:LED-0603")
      (libsource (lib "eagle-import") (part "LED0603"))
    )
    (comp (ref "D343")
      (value "HOUR")
      (footprint "eagle-import:LED-0603")
      (libsource (lib "eagle-import") (part "LED0603"))
    )
    (comp (ref "D344")
      (value "HOUR")
      (footprint "eagle-import:LED-0603")
      (libsource (lib "eagle-import") (part "LED0603"))
    )
    (comp (ref "D345")
      (value "HOUR")
      (footprint "eagle-import:LED-0603")
      (libsource (lib "eagle-import") (part "LED0603"))
    )
    (comp (ref "D346")
      (value "HOUR")
      (footprint "eagle-import:LED-0603")
      (libsource (lib "eagle-import") (part "LED0603"))
    )
    (comp (ref "D347")
      (value "HOUR")
      (footprint "eagle-import:LED-0603")
      (libsource (lib "eagle-import") (part "LED0603"))
    )
    (comp (ref "D348")
      (value "HOUR")
      (footprint "eagle-import:LED-0603")
      (libsource (lib "eagle-import") (part "LED0603"))
    )
    (comp (ref "D349")
      (value "HOUR")
      (footprint "eagle-import:LED-0603")
      (libsource (lib "eagle-import") (part "LED0603"))
    )
    (comp (ref "D350")
      (value "HOUR")
      (footprint "eagle-import:LED-0603")
      (libsource (lib "eagle-import") (part "LED0603"))
    )
    (comp (ref "D351")
      (value "HOUR")
      (footprint "eagle-import:LED-0603")
      (libsource (lib "eagle-import") (part "LED0603"))
    )
    (comp (ref "D352")
      (value "HOUR")
      (footprint "eagle-import:LED-0603")
      (libsource (lib "eagle-import") (part "LED0603"))
    )
    (comp (ref "D353")
      (value "HOUR")
      (footprint "eagle-import:LED-0603")
      (libsource (lib "eagle-import") (part "LED0603"))
    )
    (comp (ref "D354")
      (value "HOUR")
      (footprint "eagle-import:LED-0603")
      (libsource (lib "eagle-import") (part "LED0603"))
    )
    (comp (ref "D355")
      (value "HOUR")
      (footprint "eagle-import:LED-0603")
      (libsource (lib "eagle-import") (part "LED0603"))
    )
    (comp (ref "D356")
      (value "HOUR")
      (footprint "eagle-import:LED-0603")
      (libsource (lib "eagle-import") (part "LED0603"))
    )
    (comp (ref "D357")
      (value "HOUR")
      (footprint "eagle-import:LED-0603")
      (libsource (lib "eagle-import") (part "LED0603"))
    )
    (comp (ref "D358")
      (value "HOUR")
      (footprint "eagle-import:LED-0603")
      (libsource (lib "eagle-import") (part "LED0603"))
    )
    (comp (ref "D359")
      (value "HOUR")
      (footprint "eagle-import:LED-0603")
      (libsource (lib "eagle-import") (part "LED0603"))
    )
    (comp (ref "D501")
      (value "RED")
      (footprint "eagle-import:LED-0603")
      (libsource (lib "eagle-import") (part "LED0603"))
    )
    (comp (ref "D502")
      (value "BLUE")
      (footprint "eagle-import:LED-0603")
      (libsource (lib "eagle-import") (part "LED0603"))
    )
    (comp (ref "J002")
      (value "M04PTH")
      (footprint "eagle-import:1X04")
      (libsource (lib "eagle-import") (part "M04PTH"))
    )
    (comp (ref "J003")
      (value "M06SIP")
      (footprint "eagle-import:1X06")
      (libsource (lib "eagle-import") (part "M06SIP"))
    )
    (comp (ref "J402")
      (value "EM406")
      (footprint "eagle-import:EM406")
      (libsource (lib "eagle-import") (part "EM406"))
    )
    (comp (ref "J404")
      (value "EM406")
      (footprint "eagle-import:EM406")
      (libsource (lib "eagle-import") (part "EM406"))
    )
    (comp (ref "R1")
      (value "47")
      (footprint "eagle-import:CRA04")
      (libsource (lib "eagle-import") (part "RP404"))
    )
    (comp (ref "R2")
      (value "47")
      (footprint "eagle-import:CRA04")
      (libsource (lib "eagle-import") (part "RP404"))
    )
    (comp (ref "R3")
      (value "47")
      (footprint "eagle-import:CRA04")
      (libsource (lib "eagle-import") (part "RP404"))
    )
    (comp (ref "R4")
      (value "47")
      (footprint "eagle-import:CRA04")
      (libsource (lib "eagle-import") (part "RP404"))
    )
    (comp (ref "R501")
      (value "680")
      (footprint "eagle-import:0603-RES")
      (libsource (lib "eagle-import") (part "RESISTOR0603-RES"))
    )
    (comp (ref "R502")
      (value "680")
      (footprint "eagle-import:0603-RES")
      (libsource (lib "eagle-import") (part "RESISTOR0603-RES"))
    )
    (comp (ref "R606")
      (value "10k")
      (footprint "eagle-import:CRA04")
      (libsource (lib "eagle-import") (part "RP404"))
    )
    (comp (ref "S429")
      (value "B3U-1100P")
      (footprint "eagle-import:B3U-1100P")
      (libsource (lib "eagle-import") (part "B3U-1100P"))
    )
    (comp (ref "SJ1")
      (value "SOLDERJUMPER_2WAYS")
      (footprint "eagle-import:SJ_3")
      (libsource (lib "eagle-import") (part "SOLDERJUMPER_2WAYS"))
    )
    (comp (ref "U401")
      (value "ATMEGA328")
      (footprint "eagle-import:TQFP32-08")
      (libsource (lib "eagle-import") (part "ATMEGA168"))
    )
    (comp (ref "U501")
      (value "FT232RLSSOP")
      (footprint "eagle-import:SSOP28DB")
      (libsource (lib "eagle-import") (part "FT232RLSSOP"))
    )
    (comp (ref "U602")
      (value "ZF7")
      (footprint "eagle-import:SC-70-6")
      (libsource (lib "eagle-import") (part "NC7SZ157"))
    )
    (comp (ref "Y401")
      (value "12.00")
      (footprint "eagle-import:CRYSTAL_SMD")
      (libsource (lib "eagle-import") (part "TSX-3225"))
    )
  )
  (nets
    (net (code "1") (name "/AT_RX") (class "Default")
      (node (ref "SJ1") (pin "2") (pinfunction "2_2") (pintype "passive"))
      (node (ref "U401") (pin "30") (pinfunction "PD0(RXD)_30") (pintype "bidirectional"))
      (node (ref "U602") (pin "4") (pinfunction "OUT_4") (pintype "bidirectional"))
    )
    (net (code "2") (name "/AT_TX") (class "Default")
      (node (ref "J402") (pin "3") (pinfunction "RX_3") (pintype "bidirectional"))
      (node (ref "J404") (pin "3") (pinfunction "RX_3") (pintype "bidirectional"))
      (node (ref "U401") (pin "31") (pinfunction "PD1(TXD)_31") (pintype "bidirectional"))
      (node (ref "U501") (pin "5") (pinfunction "RXD_5") (pintype "input"))
    )
    (net (code "3") (name "/D12") (class "Default")
      (node (ref "J003") (pin "5") (pinfunction "5_5") (pintype "passive"))
      (node (ref "R606") (pin "8") (pinfunction "2_8") (pintype "passive"))
      (node (ref "U401") (pin "16") (pinfunction "PB4(MISO)_16") (pintype "bidirectional"))
      (node (ref "U602") (pin "6") (pinfunction "SEL_6") (pintype "bidirectional"))
    )
    (net (code "4") (name "/GPS_TX") (class "Default")
      (node (ref "J402") (pin "4") (pinfunction "TX_4") (pintype "bidirectional"))
      (node (ref "J404") (pin "4") (pinfunction "TX_4") (pintype "bidirectional"))
      (node (ref "SJ1") (pin "1") (pinfunction "1_1") (pintype "passive"))
      (node (ref "U602") (pin "3") (pinfunction "I0_3") (pintype "bidirectional"))
    )
    (net (code "5") (name "/P01") (class "Default")
      (node (ref "J003") (pin "6") (pinfunction "6_6") (pintype "passive"))
      (node (ref "R1") (pin "1") (pinfunction "1_1") (pintype "passive"))
      (node (ref "U401") (pin "15") (pinfunction "PB3(MOSI/OC2)_15") (pintype "bidirectional"))
    )
    (net (code "6") (name "/P02") (class "Default")
      (node (ref "R1") (pin "2") (pinfunction "1_2") (pintype "passive"))
      (node (ref "U401") (pin "2") (pinfunction "PD4(XCK/T0)_2") (pintype "bidirectional"))
    )
    (net (code "7") (name "/P03") (class "Default")
      (node (ref "R1") (pin "3") (pinfunction "1_3") (pintype "passive"))
      (node (ref "U401") (pin "14") (pinfunction "PB2(SS/OC1B)_14") (pintype "bidirectional"))
    )
    (net (code "8") (name "/P04") (class "Default")
      (node (ref "R1") (pin "4") (pinfunction "1_4") (pintype "passive"))
      (node (ref "U401") (pin "13") (pinfunction "PB1(OC1A)_13") (pintype "bidirectional"))
    )
    (net (code "9") (name "/P05") (class "Default")
      (node (ref "R2") (pin "1") (pinfunction "1_1") (pintype "passive"))
      (node (ref "U401") (pin "12") (pinfunction "PB0(ICP)_12") (pintype "bidirectional"))
    )
    (net (code "10") (name "/P06") (class "Default")
      (node (ref "R2") (pin "2") (pinfunction "1_2") (pintype "passive"))
      (node (ref "U401") (pin "11") (pinfunction "PD7(AIN1)_11") (pintype "bidirectional"))
    )
    (net (code "11") (name "/P07") (class "Default")
      (node (ref "R2") (pin "3") (pinfunction "1_3") (pintype "passive"))
      (node (ref "U401") (pin "10") (pinfunction "PD6(AIN0)_10") (pintype "bidirectional"))
    )
    (net (code "12") (name "/P08") (class "Default")
      (node (ref "R2") (pin "4") (pinfunction "1_4") (pintype "passive"))
      (node (ref "U401") (pin "9") (pinfunction "PD5(T1)_9") (pintype "bidirectional"))
    )
    (net (code "13") (name "/P09") (class "Default")
      (node (ref "R3") (pin "1") (pinfunction "1_1") (pintype "passive"))
      (node (ref "U401") (pin "1") (pinfunction "PD3(INT1)_1") (pintype "bidirectional"))
    )
    (net (code "14") (name "/P10") (class "Default")
      (node (ref "R3") (pin "2") (pinfunction "1_2") (pintype "passive"))
      (node (ref "U401") (pin "28") (pinfunction "PC5(ADC5/SCL)_28") (pintype "bidirectional"))
    )
    (net (code "15") (name "/P11") (class "Default")
      (node (ref "R3") (pin "3") (pinfunction "1_3") (pintype "passive"))
      (node (ref "U401") (pin "27") (pinfunction "PC4(ADC4/SDA)_27") (pintype "bidirectional"))
    )
    (net (code "16") (name "/P12") (class "Default")
      (node (ref "R3") (pin "4") (pinfunction "1_4") (pintype "passive"))
      (node (ref "U401") (pin "26") (pinfunction "PC3(ADC3)_26") (pintype "bidirectional"))
    )
    (net (code "17") (name "/P13") (class "Default")
      (node (ref "R4") (pin "1") (pinfunction "1_1") (pintype "passive"))
      (node (ref "U401") (pin "25") (pinfunction "PC2(ADC2)_25") (pintype "bidirectional"))
    )
    (net (code "18") (name "/P14") (class "Default")
      (node (ref "R4") (pin "2") (pinfunction "1_2") (pintype "passive"))
      (node (ref "U401") (pin "24") (pinfunction "PC1(ADC1)_24") (pintype "bidirectional"))
    )
    (net (code "19") (name "/P15") (class "Default")
      (node (ref "R4") (pin "3") (pinfunction "1_3") (pintype "passive"))
      (node (ref "U401") (pin "23") (pinfunction "PC0(ADC0)_23") (pintype "bidirectional"))
    )
    (net (code "20") (name "/P16") (class "Default")
      (node (ref "J003") (pin "4") (pinfunction "4_4") (pintype "passive"))
      (node (ref "R4") (pin "4") (pinfunction "1_4") (pintype "passive"))
      (node (ref "U401") (pin "17") (pinfunction "PB5(SCK)_17") (pintype "bidirectional"))
    )
    (net (code "21") (name "/PPS") (class "Default")
      (node (ref "J402") (pin "6") (pinfunction "1PPS_6") (pintype "bidirectional"))
      (node (ref "J404") (pin "6") (pinfunction "1PPS_6") (pintype "bidirectional"))
      (node (ref "U401") (pin "32") (pinfunction "PD2(INT0)_32") (pintype "bidirectional"))
    )
    (net (code "22") (name "/Q01") (class "Default")
      (node (ref "D000") (pin "C") (pinfunction "C_C") (pintype "passive"))
      (node (ref "D015") (pin "C") (pinfunction "C_C") (pintype "passive"))
      (node (ref "D029") (pin "C") (pinfunction "C_C") (pintype "passive"))
      (node (ref "D042") (pin "C") (pinfunction "C_C") (pintype "passive"))
      (node (ref "D054") (pin "C") (pinfunction "C_C") (pintype "passive"))
      (node (ref "D105") (pin "C") (pinfunction "C_C") (pintype "passive"))
      (node (ref "D115") (pin "C") (pinfunction "C_C") (pintype "passive"))
      (node (ref "D124") (pin "C") (pinfunction "C_C") (pintype "passive"))
      (node (ref "D132") (pin "C") (pinfunction "C_C") (pintype "passive"))
      (node (ref "D139") (pin "C") (pinfunction "C_C") (pintype "passive"))
      (node (ref "D145") (pin "C") (pinfunction "C_C") (pintype "passive"))
      (node (ref "D150") (pin "C") (pinfunction "C_C") (pintype "passive"))
      (node (ref "D154") (pin "C") (pinfunction "C_C") (pintype "passive"))
      (node (ref "D157") (pin "C") (pinfunction "C_C") (pintype "passive"))
      (node (ref "D159") (pin "C") (pinfunction "C_C") (pintype "passive"))
      (node (ref "D200") (pin "A") (pinfunction "A_A") (pintype "passive"))
      (node (ref "D215") (pin "A") (pinfunction "A_A") (pintype "passive"))
      (node (ref "D229") (pin "A") (pinfunction "A_A") (pintype "passive"))
      (node (ref "D242") (pin "A") (pinfunction "A_A") (pintype "passive"))
      (node (ref "D254") (pin "A") (pinfunction "A_A") (pintype "passive"))
      (node (ref "D305") (pin "A") (pinfunction "A_A") (pintype "passive"))
      (node (ref "D315") (pin "A") (pinfunction "A_A") (pintype "passive"))
      (node (ref "D324") (pin "A") (pinfunction "A_A") (pintype "passive"))
      (node (ref "D332") (pin "A") (pinfunction "A_A") (pintype "passive"))
      (node (ref "D339") (pin "A") (pinfunction "A_A") (pintype "passive"))
      (node (ref "D345") (pin "A") (pinfunction "A_A") (pintype "passive"))
      (node (ref "D350") (pin "A") (pinfunction "A_A") (pintype "passive"))
      (node (ref "D354") (pin "A") (pinfunction "A_A") (pintype "passive"))
      (node (ref "D357") (pin "A") (pinfunction "A_A") (pintype "passive"))
      (node (ref "D359") (pin "A") (pinfunction "A_A") (pintype "passive"))
      (node (ref "R1") (pin "8") (pinfunction "2_8") (pintype "passive"))
    )
    (net (code "23") (name "/Q02") (class "Default")
      (node (ref "D000") (pin "A") (pinfunction "A_A") (pintype "passive"))
      (node (ref "D001") (pin "C") (pinfunction "C_C") (pintype "passive"))
      (node (ref "D016") (pin "C") (pinfunction "C_C") (pintype "passive"))
      (node (ref "D030") (pin "C") (pinfunction "C_C") (pintype "passive"))
      (node (ref "D043") (pin "C") (pinfunction "C_C") (pintype "passive"))
      (node (ref "D055") (pin "C") (pinfunction "C_C") (pintype "passive"))
      (node (ref "D106") (pin "C") (pinfunction "C_C") (pintype "passive"))
      (node (ref "D116") (pin "C") (pinfunction "C_C") (pintype "passive"))
      (node (ref "D125") (pin "C") (pinfunction "C_C") (pintype "passive"))
      (node (ref "D133") (pin "C") (pinfunction "C_C") (pintype "passive"))
      (node (ref "D140") (pin "C") (pinfunction "C_C") (pintype "passive"))
      (node (ref "D146") (pin "C") (pinfunction "C_C") (pintype "passive"))
      (node (ref "D151") (pin "C") (pinfunction "C_C") (pintype "passive"))
      (node (ref "D155") (pin "C") (pinfunction "C_C") (pintype "passive"))
      (node (ref "D158") (pin "C") (pinfunction "C_C") (pintype "passive"))
      (node (ref "D200") (pin "C") (pinfunction "C_C") (pintype "passive"))
      (node (ref "D201") (pin "A") (pinfunction "A_A") (pintype "passive"))
      (node (ref "D216") (pin "A") (pinfunction "A_A") (pintype "passive"))
      (node (ref "D230") (pin "A") (pinfunction "A_A") (pintype "passive"))
      (node (ref "D243") (pin "A") (pinfunction "A_A") (pintype "passive"))
      (node (ref "D255") (pin "A") (pinfunction "A_A") (pintype "passive"))
      (node (ref "D306") (pin "A") (pinfunction "A_A") (pintype "passive"))
      (node (ref "D316") (pin "A") (pinfunction "A_A") (pintype "passive"))
      (node (ref "D325") (pin "A") (pinfunction "A_A") (pintype "passive"))
      (node (ref "D333") (pin "A") (pinfunction "A_A") (pintype "passive"))
      (node (ref "D340") (pin "A") (pinfunction "A_A") (pintype "passive"))
      (node (ref "D346") (pin "A") (pinfunction "A_A") (pintype "passive"))
      (node (ref "D351") (pin "A") (pinfunction "A_A") (pintype "passive"))
      (node (ref "D355") (pin "A") (pinfunction "A_A") (pintype "passive"))
      (node (ref "D358") (pin "A") (pinfunction "A_A") (pintype "passive"))
      (node (ref "R1") (pin "7") (pinfunction "2_7") (pintype "passive"))
    )
    (net (code "24") (name "/Q03") (class "Default")
      (node (ref "D001") (pin "A") (pinfunction "A_A") (pintype "passive"))
      (node (ref "D002") (pin "C") (pinfunction "C_C") (pintype "passive"))
      (node (ref "D015") (pin "A") (pinfunction "A_A") (pintype "passive"))
      (node (ref "D017") (pin "C") (pinfunction "C_C") (pintype "passive"))
      (node (ref "D031") (pin "C") (pinfunction "C_C") (pintype "passive"))
      (node (ref "D044") (pin "C") (pinfunction "C_C") (pintype "passive"))
      (node (ref "D056") (pin "C") (pinfunction "C_C") (pintype "passive"))
      (node (ref "D107") (pin "C") (pinfunction "C_C") (pintype "passive"))
      (node (ref "D117") (pin "C") (pinfunction "C_C") (pintype "passive"))
      (node (ref "D126") (pin "C") (pinfunction "C_C") (pintype "passive"))
      (node (ref "D134") (pin "C") (pinfunction "C_C") (pintype "passive"))
      (node (ref "D141") (pin "C") (pinfunction "C_C") (pintype "passive"))
      (node (ref "D147") (pin "C") (pinfunction "C_C") (pintype "passive"))
      (node (ref "D152") (pin "C") (pinfunction "C_C") (pintype "passive"))
      (node (ref "D156") (pin "C") (pinfunction "C_C") (pintype "passive"))
      (node (ref "D201") (pin "C") (pinfunction "C_C") (pintype "passive"))
      (node (ref "D202") (pin "A") (pinfunction "A_A") (pintype "passive"))
      (node (ref "D215") (pin "C") (pinfunction "C_C") (pintype "passive"))
      (node (ref "D217") (pin "A") (pinfunction "A_A") (pintype "passive"))
      (node (ref "D231") (pin "A") (pinfunction "A_A") (pintype "passive"))
      (node (ref "D244") (pin "A") (pinfunction "A_A") (pintype "passive"))
      (node (ref "D256") (pin "A") (pinfunction "A_A") (pintype "passive"))
      (node (ref "D307") (pin "A") (pinfunction "A_A") (pintype "passive"))
      (node (ref "D317") (pin "A") (pinfunction "A_A") (pintype "passive"))
      (node (ref "D326") (pin "A") (pinfunction "A_A") (pintype "passive"))
      (node (ref "D334") (pin "A") (pinfunction "A_A") (pintype "passive"))
      (node (ref "D341") (pin "A") (pinfunction "A_A") (pintype "passive"))
      (node (ref "D347") (pin "A") (pinfunction "A_A") (pintype "passive"))
      (node (ref "D352") (pin "A") (pinfunction "A_A") (pintype "passive"))
      (node (ref "D356") (pin "A") (pinfunction "A_A") (pintype "passive"))
      (node (ref "R1") (pin "6") (pinfunction "2_6") (pintype "passive"))
    )
    (net (code "25") (name "/Q04") (class "Default")
      (node (ref "D002") (pin "A") (pinfunction "A_A") (pintype "passive"))
      (node (ref "D003") (pin "C") (pinfunction "C_C") (pintype "passive"))
      (node (ref "D016") (pin "A") (pinfunction "A_A") (pintype "passive"))
      (node (ref "D018") (pin "C") (pinfunction "C_C") (pintype "passive"))
      (node (ref "D029") (pin "A") (pinfunction "A_A") (pintype "passive"))
      (node (ref "D032") (pin "C") (pinfunction "C_C") (pintype "passive"))
      (node (ref "D045") (pin "C") (pinfunction "C_C") (pintype "passive"))
      (node (ref "D057") (pin "C") (pinfunction "C_C") (pintype "passive"))
      (node (ref "D108") (pin "C") (pinfunction "C_C") (pintype "passive"))
      (node (ref "D118") (pin "C") (pinfunction "C_C") (pintype "passive"))
      (node (ref "D127") (pin "C") (pinfunction "C_C") (pintype "passive"))
      (node (ref "D135") (pin "C") (pinfunction "C_C") (pintype "passive"))
      (node (ref "D142") (pin "C") (pinfunction "C_C") (pintype "passive"))
      (node (ref "D148") (pin "C") (pinfunction "C_C") (pintype "passive"))
      (node (ref "D153") (pin "C") (pinfunction "C_C") (pintype "passive"))
      (node (ref "D202") (pin "C") (pinfunction "C_C") (pintype "passive"))
      (node (ref "D203") (pin "A") (pinfunction "A_A") (pintype "passive"))
      (node (ref "D216") (pin "C") (pinfunction "C_C") (pintype "passive"))
      (node (ref "D218") (pin "A") (pinfunction "A_A") (pintype "passive"))
      (node (ref "D229") (pin "C") (pinfunction "C_C") (pintype "passive"))
      (node (ref "D232") (pin "A") (pinfunction "A_A") (pintype "passive"))
      (node (ref "D245") (pin "A") (pinfunction "A_A") (pintype "passive"))
      (node (ref "D257") (pin "A") (pinfunction "A_A") (pintype "passive"))
      (node (ref "D308") (pin "A") (pinfunction "A_A") (pintype "passive"))
      (node (ref "D318") (pin "A") (pinfunction "A_A") (pintype "passive"))
      (node (ref "D327") (pin "A") (pinfunction "A_A") (pintype "passive"))
      (node (ref "D335") (pin "A") (pinfunction "A_A") (pintype "passive"))
      (node (ref "D342") (pin "A") (pinfunction "A_A") (pintype "passive"))
      (node (ref "D348") (pin "A") (pinfunction "A_A") (pintype "passive"))
      (node (ref "D353") (pin "A") (pinfunction "A_A") (pintype "passive"))
      (node (ref "R1") (pin "5") (pinfunction "2_5") (pintype "passive"))
    )
    (net (code "26") (name "/Q05") (class "Default")
      (node (ref "D003") (pin "A") (pinfunction "A_A") (pintype "passive"))
      (node (ref "D004") (pin "C") (pinfunction "C_C") (pintype "passive"))
      (node (ref "D017") (pin "A") (pinfunction "A_A") (pintype "passive"))
      (node (ref "D019") (pin "C") (pinfunction "C_C") (pintype "passive"))
      (node (ref "D030") (pin "A") (pinfunction "A_A") (pintype "passive"))
      (node (ref "D033") (pin "C") (pinfunction "C_C") (pintype "passive"))
      (node (ref "D042") (pin "A") (pinfunction "A_A") (pintype "passive"))
      (node (ref "D046") (pin "C") (pinfunction "C_C") (pintype "passive"))
      (node (ref "D058") (pin "C") (pinfunction "C_C") (pintype "passive"))
      (node (ref "D109") (pin "C") (pinfunction "C_C") (pintype "passive"))
      (node (ref "D119") (pin "C") (pinfunction "C_C") (pintype "passive"))
      (node (ref "D128") (pin "C") (pinfunction "C_C") (pintype "passive"))
      (node (ref "D136") (pin "C") (pinfunction "C_C") (pintype "passive"))
      (node (ref "D143") (pin "C") (pinfunction "C_C") (pintype "passive"))
      (node (ref "D149") (pin "C") (pinfunction "C_C") (pintype "passive"))
      (node (ref "D203") (pin "C") (pinfunction "C_C") (pintype "passive"))
      (node (ref "D204") (pin "A") (pinfunction "A_A") (pintype "passive"))
      (node (ref "D217") (pin "C") (pinfunction "C_C") (pintype "passive"))
      (node (ref "D219") (pin "A") (pinfunction "A_A") (pintype "passive"))
      (node (ref "D230") (pin "C") (pinfunction "C_C") (pintype "passive"))
      (node (ref "D233") (pin "A") (pinfunction "A_A") (pintype "passive"))
      (node (ref "D242") (pin "C") (pinfunction "C_C") (pintype "passive"))
      (node (ref "D246") (pin "A") (pinfunction "A_A") (pintype "passive"))
      (node (ref "D258") (pin "A") (pinfunction "A_A") (pintype "passive"))
      (node (ref "D309") (pin "A") (pinfunction "A_A") (pintype "passive"))
      (node (ref "D319") (pin "A") (pinfunction "A_A") (pintype "passive"))
      (node (ref "D328") (pin "A") (pinfunction "A_A") (pintype "passive"))
      (node (ref "D336") (pin "A") (pinfunction "A_A") (pintype "passive"))
      (node (ref "D343") (pin "A") (pinfunction "A_A") (pintype "passive"))
      (node (ref "D349") (pin "A") (pinfunction "A_A") (pintype "passive"))
      (node (ref "R2") (pin "8") (pinfunction "2_8") (pintype "passive"))
    )
    (net (code "27") (name "/Q06") (class "Default")
      (node (ref "D004") (pin "A") (pinfunction "A_A") (pintype "passive"))
      (node (ref "D005") (pin "C") (pinfunction "C_C") (pintype "passive"))
      (node (ref "D018") (pin "A") (pinfunction "A_A") (pintype "passive"))
      (node (ref "D020") (pin "C") (pinfunction "C_C") (pintype "passive"))
      (node (ref "D031") (pin "A") (pinfunction "A_A") (pintype "passive"))
      (node (ref "D034") (pin "C") (pinfunction "C_C") (pintype "passive"))
      (node (ref "D043") (pin "A") (pinfunction "A_A") (pintype "passive"))
      (node (ref "D047") (pin "C") (pinfunction "C_C") (pintype "passive"))
      (node (ref "D054") (pin "A") (pinfunction "A_A") (pintype "passive"))
      (node (ref "D059") (pin "C") (pinfunction "C_C") (pintype "passive"))
      (node (ref "D110") (pin "C") (pinfunction "C_C") (pintype "passive"))
      (node (ref "D120") (pin "C") (pinfunction "C_C") (pintype "passive"))
      (node (ref "D129") (pin "C") (pinfunction "C_C") (pintype "passive"))
      (node (ref "D137") (pin "C") (pinfunction "C_C") (pintype "passive"))
      (node (ref "D144") (pin "C") (pinfunction "C_C") (pintype "passive"))
      (node (ref "D204") (pin "C") (pinfunction "C_C") (pintype "passive"))
      (node (ref "D205") (pin "A") (pinfunction "A_A") (pintype "passive"))
      (node (ref "D218") (pin "C") (pinfunction "C_C") (pintype "passive"))
      (node (ref "D220") (pin "A") (pinfunction "A_A") (pintype "passive"))
      (node (ref "D231") (pin "C") (pinfunction "C_C") (pintype "passive"))
      (node (ref "D234") (pin "A") (pinfunction "A_A") (pintype "passive"))
      (node (ref "D243") (pin "C") (pinfunction "C_C") (pintype "passive"))
      (node (ref "D247") (pin "A") (pinfunction "A_A") (pintype "passive"))
      (node (ref "D254") (pin "C") (pinfunction "C_C") (pintype "passive"))
      (node (ref "D259") (pin "A") (pinfunction "A_A") (pintype "passive"))
      (node (ref "D310") (pin "A") (pinfunction "A_A") (pintype "passive"))
      (node (ref "D320") (pin "A") (pinfunction "A_A") (pintype "passive"))
      (node (ref "D329") (pin "A") (pinfunction "A_A") (pintype "passive"))
      (node (ref "D337") (pin "A") (pinfunction "A_A") (pintype "passive"))
      (node (ref "D344") (pin "A") (pinfunction "A_A") (pintype "passive"))
      (node (ref "R2") (pin "7") (pinfunction "2_7") (pintype "passive"))
    )
    (net (code "28") (name "/Q07") (class "Default")
      (node (ref "D005") (pin "A") (pinfunction "A_A") (pintype "passive"))
      (node (ref "D006") (pin "C") (pinfunction "C_C") (pintype "passive"))
      (node (ref "D019") (pin "A") (pinfunction "A_A") (pintype "passive"))
      (node (ref "D021") (pin "C") (pinfunction "C_C") (pintype "passive"))
      (node (ref "D032") (pin "A") (pinfunction "A_A") (pintype "passive"))
      (node (ref "D035") (pin "C") (pinfunction "C_C") (pintype "passive"))
      (node (ref "D044") (pin "A") (pinfunction "A_A") (pintype "passive"))
      (node (ref "D048") (pin "C") (pinfunction "C_C") (pintype "passive"))
      (node (ref "D055") (pin "A") (pinfunction "A_A") (pintype "passive"))
      (node (ref "D100") (pin "C") (pinfunction "C_C") (pintype "passive"))
      (node (ref "D105") (pin "A") (pinfunction "A_A") (pintype "passive"))
      (node (ref "D111") (pin "C") (pinfunction "C_C") (pintype "passive"))
      (node (ref "D121") (pin "C") (pinfunction "C_C") (pintype "passive"))
      (node (ref "D130") (pin "C") (pinfunction "C_C") (pintype "passive"))
      (node (ref "D138") (pin "C") (pinfunction "C_C") (pintype "passive"))
      (node (ref "D205") (pin "C") (pinfunction "C_C") (pintype "passive"))
      (node (ref "D206") (pin "A") (pinfunction "A_A") (pintype "passive"))
      (node (ref "D219") (pin "C") (pinfunction "C_C") (pintype "passive"))
      (node (ref "D221") (pin "A") (pinfunction "A_A") (pintype "passive"))
      (node (ref "D232") (pin "C") (pinfunction "C_C") (pintype "passive"))
      (node (ref "D235") (pin "A") (pinfunction "A_A") (pintype "passive"))
      (node (ref "D244") (pin "C") (pinfunction "C_C") (pintype "passive"))
      (node (ref "D248") (pin "A") (pinfunction "A_A") (pintype "passive"))
      (node (ref "D255") (pin "C") (pinfunction "C_C") (pintype "passive"))
      (node (ref "D300") (pin "A") (pinfunction "A_A") (pintype "passive"))
      (node (ref "D305") (pin "C") (pinfunction "C_C") (pintype "passive"))
      (node (ref "D311") (pin "A") (pinfunction "A_A") (pintype "passive"))
      (node (ref "D321") (pin "A") (pinfunction "A_A") (pintype "passive"))
      (node (ref "D330") (pin "A") (pinfunction "A_A") (pintype "passive"))
      (node (ref "D338") (pin "A") (pinfunction "A_A") (pintype "passive"))
      (node (ref "R2") (pin "6") (pinfunction "2_6") (pintype "passive"))
    )
    (net (code "29") (name "/Q08") (class "Default")
      (node (ref "D006") (pin "A") (pinfunction "A_A") (pintype "passive"))
      (node (ref "D007") (pin "C") (pinfunction "C_C") (pintype "passive"))
      (node (ref "D020") (pin "A") (pinfunction "A_A") (pintype "passive"))
      (node (ref "D022") (pin "C") (pinfunction "C_C") (pintype "passive"))
      (node (ref "D033") (pin "A") (pinfunction "A_A") (pintype "passive"))
      (node (ref "D036") (pin "C") (pinfunction "C_C") (pintype "passive"))
      (node (ref "D045") (pin "A") (pinfunction "A_A") (pintype "passive"))
      (node (ref "D049") (pin "C") (pinfunction "C_C") (pintype "passive"))
      (node (ref "D056") (pin "A") (pinfunction "A_A") (pintype "passive"))
      (node (ref "D101") (pin "C") (pinfunction "C_C") (pintype "passive"))
      (node (ref "D106") (pin "A") (pinfunction "A_A") (pintype "passive"))
      (node (ref "D112") (pin "C") (pinfunction "C_C") (pintype "passive"))
      (node (ref "D115") (pin "A") (pinfunction "A_A") (pintype "passive"))
      (node (ref "D122") (pin "C") (pinfunction "C_C") (pintype "passive"))
      (node (ref "D131") (pin "C") (pinfunction "C_C") (pintype "passive"))
      (node (ref "D206") (pin "C") (pinfunction "C_C") (pintype "passive"))
      (node (ref "D207") (pin "A") (pinfunction "A_A") (pintype "passive"))
      (node (ref "D220") (pin "C") (pinfunction "C_C") (pintype "passive"))
      (node (ref "D222") (pin "A") (pinfunction "A_A") (pintype "passive"))
      (node (ref "D233") (pin "C") (pinfunction "C_C") (pintype "passive"))
      (node (ref "D236") (pin "A") (pinfunction "A_A") (pintype "passive"))
      (node (ref "D245") (pin "C") (pinfunction "C_C") (pintype "passive"))
      (node (ref "D249") (pin "A") (pinfunction "A_A") (pintype "passive"))
      (node (ref "D256") (pin "C") (pinfunction "C_C") (pintype "passive"))
      (node (ref "D301") (pin "A") (pinfunction "A_A") (pintype "passive"))
      (node (ref "D306") (pin "C") (pinfunction "C_C") (pintype "passive"))
      (node (ref "D312") (pin "A") (pinfunction "A_A") (pintype "passive"))
      (node (ref "D315") (pin "C") (pinfunction "C_C") (pintype "passive"))
      (node (ref "D322") (pin "A") (pinfunction "A_A") (pintype "passive"))
      (node (ref "D331") (pin "A") (pinfunction "A_A") (pintype "passive"))
      (node (ref "R2") (pin "5") (pinfunction "2_5") (pintype "passive"))
    )
    (net (code "30") (name "/Q09") (class "Default")
      (node (ref "D007") (pin "A") (pinfunction "A_A") (pintype "passive"))
      (node (ref "D008") (pin "C") (pinfunction "C_C") (pintype "passive"))
      (node (ref "D021") (pin "A") (pinfunction "A_A") (pintype "passive"))
      (node (ref "D023") (pin "C") (pinfunction "C_C") (pintype "passive"))
      (node (ref "D034") (pin "A") (pinfunction "A_A") (pintype "passive"))
      (node (ref "D037") (pin "C") (pinfunction "C_C") (pintype "passive"))
      (node (ref "D046") (pin "A") (pinfunction "A_A") (pintype "passive"))
      (node (ref "D050") (pin "C") (pinfunction "C_C") (pintype "passive"))
      (node (ref "D057") (pin "A") (pinfunction "A_A") (pintype "passive"))
      (node (ref "D102") (pin "C") (pinfunction "C_C") (pintype "passive"))
      (node (ref "D107") (pin "A") (pinfunction "A_A") (pintype "passive"))
      (node (ref "D113") (pin "C") (pinfunction "C_C") (pintype "passive"))
      (node (ref "D116") (pin "A") (pinfunction "A_A") (pintype "passive"))
      (node (ref "D123") (pin "C") (pinfunction "C_C") (pintype "passive"))
      (node (ref "D124") (pin "A") (pinfunction "A_A") (pintype "passive"))
      (node (ref "D207") (pin "C") (pinfunction "C_C") (pintype "passive"))
      (node (ref "D208") (pin "A") (pinfunction "A_A") (pintype "passive"))
      (node (ref "D221") (pin "C") (pinfunction "C_C") (pintype "passive"))
      (node (ref "D223") (pin "A") (pinfunction "A_A") (pintype "passive"))
      (node (ref "D234") (pin "C") (pinfunction "C_C") (pintype "passive"))
      (node (ref "D237") (pin "A") (pinfunction "A_A") (pintype "passive"))
      (node (ref "D246") (pin "C") (pinfunction "C_C") (pintype "passive"))
      (node (ref "D250") (pin "A") (pinfunction "A_A") (pintype "passive"))
      (node (ref "D257") (pin "C") (pinfunction "C_C") (pintype "passive"))
      (node (ref "D302") (pin "A") (pinfunction "A_A") (pintype "passive"))
      (node (ref "D307") (pin "C") (pinfunction "C_C") (pintype "passive"))
      (node (ref "D313") (pin "A") (pinfunction "A_A") (pintype "passive"))
      (node (ref "D316") (pin "C") (pinfunction "C_C") (pintype "passive"))
      (node (ref "D323") (pin "A") (pinfunction "A_A") (pintype "passive"))
      (node (ref "D324") (pin "C") (pinfunction "C_C") (pintype "passive"))
      (node (ref "R3") (pin "8") (pinfunction "2_8") (pintype "passive"))
    )
    (net (code "31") (name "/Q10") (class "Default")
      (node (ref "D008") (pin "A") (pinfunction "A_A") (pintype "passive"))
      (node (ref "D009") (pin "C") (pinfunction "C_C") (pintype "passive"))
      (node (ref "D022") (pin "A") (pinfunction "A_A") (pintype "passive"))
      (node (ref "D024") (pin "C") (pinfunction "C_C") (pintype "passive"))
      (node (ref "D035") (pin "A") (pinfunction "A_A") (pintype "passive"))
      (node (ref "D038") (pin "C") (pinfunction "C_C") (pintype "passive"))
      (node (ref "D047") (pin "A") (pinfunction "A_A") (pintype "passive"))
      (node (ref "D051") (pin "C") (pinfunction "C_C") (pintype "passive"))
      (node (ref "D058") (pin "A") (pinfunction "A_A") (pintype "passive"))
      (node (ref "D103") (pin "C") (pinfunction "C_C") (pintype "passive"))
      (node (ref "D108") (pin "A") (pinfunction "A_A") (pintype "passive"))
      (node (ref "D114") (pin "C") (pinfunction "C_C") (pintype "passive"))
      (node (ref "D117") (pin "A") (pinfunction "A_A") (pintype "passive"))
      (node (ref "D125") (pin "A") (pinfunction "A_A") (pintype "passive"))
      (node (ref "D132") (pin "A") (pinfunction "A_A") (pintype "passive"))
      (node (ref "D208") (pin "C") (pinfunction "C_C") (pintype "passive"))
      (node (ref "D209") (pin "A") (pinfunction "A_A") (pintype "passive"))
      (node (ref "D222") (pin "C") (pinfunction "C_C") (pintype "passive"))
      (node (ref "D224") (pin "A") (pinfunction "A_A") (pintype "passive"))
      (node (ref "D235") (pin "C") (pinfunction "C_C") (pintype "passive"))
      (node (ref "D238") (pin "A") (pinfunction "A_A") (pintype "passive"))
      (node (ref "D247") (pin "C") (pinfunction "C_C") (pintype "passive"))
      (node (ref "D251") (pin "A") (pinfunction "A_A") (pintype "passive"))
      (node (ref "D258") (pin "C") (pinfunction "C_C") (pintype "passive"))
      (node (ref "D303") (pin "A") (pinfunction "A_A") (pintype "passive"))
      (node (ref "D308") (pin "C") (pinfunction "C_C") (pintype "passive"))
      (node (ref "D314") (pin "A") (pinfunction "A_A") (pintype "passive"))
      (node (ref "D317") (pin "C") (pinfunction "C_C") (pintype "passive"))
      (node (ref "D325") (pin "C") (pinfunction "C_C") (pintype "passive"))
      (node (ref "D332") (pin "C") (pinfunction "C_C") (pintype "passive"))
      (node (ref "R3") (pin "7") (pinfunction "2_7") (pintype "passive"))
    )
    (net (code "32") (name "/Q11") (class "Default")
      (node (ref "D009") (pin "A") (pinfunction "A_A") (pintype "passive"))
      (node (ref "D010") (pin "C") (pinfunction "C_C") (pintype "passive"))
      (node (ref "D023") (pin "A") (pinfunction "A_A") (pintype "passive"))
      (node (ref "D025") (pin "C") (pinfunction "C_C") (pintype "passive"))
      (node (ref "D036") (pin "A") (pinfunction "A_A") (pintype "passive"))
      (node (ref "D039") (pin "C") (pinfunction "C_C") (pintype "passive"))
      (node (ref "D048") (pin "A") (pinfunction "A_A") (pintype "passive"))
      (node (ref "D052") (pin "C") (pinfunction "C_C") (pintype "passive"))
      (node (ref "D059") (pin "A") (pinfunction "A_A") (pintype "passive"))
      (node (ref "D104") (pin "C") (pinfunction "C_C") (pintype "passive"))
      (node (ref "D109") (pin "A") (pinfunction "A_A") (pintype "passive"))
      (node (ref "D118") (pin "A") (pinfunction "A_A") (pintype "passive"))
      (node (ref "D126") (pin "A") (pinfunction "A_A") (pintype "passive"))
      (node (ref "D133") (pin "A") (pinfunction "A_A") (pintype "passive"))
      (node (ref "D139") (pin "A") (pinfunction "A_A") (pintype "passive"))
      (node (ref "D209") (pin "C") (pinfunction "C_C") (pintype "passive"))
      (node (ref "D210") (pin "A") (pinfunction "A_A") (pintype "passive"))
      (node (ref "D223") (pin "C") (pinfunction "C_C") (pintype "passive"))
      (node (ref "D225") (pin "A") (pinfunction "A_A") (pintype "passive"))
      (node (ref "D236") (pin "C") (pinfunction "C_C") (pintype "passive"))
      (node (ref "D239") (pin "A") (pinfunction "A_A") (pintype "passive"))
      (node (ref "D248") (pin "C") (pinfunction "C_C") (pintype "passive"))
      (node (ref "D252") (pin "A") (pinfunction "A_A") (pintype "passive"))
      (node (ref "D259") (pin "C") (pinfunction "C_C") (pintype "passive"))
      (node (ref "D304") (pin "A") (pinfunction "A_A") (pintype "passive"))
      (node (ref "D309") (pin "C") (pinfunction "C_C") (pintype "passive"))
      (node (ref "D318") (pin "C") (pinfunction "C_C") (pintype "passive"))
      (node (ref "D326") (pin "C") (pinfunction "C_C") (pintype "passive"))
      (node (ref "D333") (pin "C") (pinfunction "C_C") (pintype "passive"))
      (node (ref "D339") (pin "C") (pinfunction "C_C") (pintype "passive"))
      (node (ref "R3") (pin "6") (pinfunction "2_6") (pintype "passive"))
    )
    (net (code "33") (name "/Q12") (class "Default")
      (node (ref "D010") (pin "A") (pinfunction "A_A") (pintype "passive"))
      (node (ref "D011") (pin "C") (pinfunction "C_C") (pintype "passive"))
      (node (ref "D024") (pin "A") (pinfunction "A_A") (pintype "passive"))
      (node (ref "D026") (pin "C") (pinfunction "C_C") (pintype "passive"))
      (node (ref "D037") (pin "A") (pinfunction "A_A") (pintype "passive"))
      (node (ref "D040") (pin "C") (pinfunction "C_C") (pintype "passive"))
      (node (ref "D049") (pin "A") (pinfunction "A_A") (pintype "passive"))
      (node (ref "D053") (pin "C") (pinfunction "C_C") (pintype "passive"))
      (node (ref "D100") (pin "A") (pinfunction "A_A") (pintype "passive"))
      (node (ref "D110") (pin "A") (pinfunction "A_A") (pintype "passive"))
      (node (ref "D119") (pin "A") (pinfunction "A_A") (pintype "passive"))
      (node (ref "D127") (pin "A") (pinfunction "A_A") (pintype "passive"))
      (node (ref "D134") (pin "A") (pinfunction "A_A") (pintype "passive"))
      (node (ref "D140") (pin "A") (pinfunction "A_A") (pintype "passive"))
      (node (ref "D145") (pin "A") (pinfunction "A_A") (pintype "passive"))
      (node (ref "D210") (pin "C") (pinfunction "C_C") (pintype "passive"))
      (node (ref "D211") (pin "A") (pinfunction "A_A") (pintype "passive"))
      (node (ref "D224") (pin "C") (pinfunction "C_C") (pintype "passive"))
      (node (ref "D226") (pin "A") (pinfunction "A_A") (pintype "passive"))
      (node (ref "D237") (pin "C") (pinfunction "C_C") (pintype "passive"))
      (node (ref "D240") (pin "A") (pinfunction "A_A") (pintype "passive"))
      (node (ref "D249") (pin "C") (pinfunction "C_C") (pintype "passive"))
      (node (ref "D253") (pin "A") (pinfunction "A_A") (pintype "passive"))
      (node (ref "D300") (pin "C") (pinfunction "C_C") (pintype "passive"))
      (node (ref "D310") (pin "C") (pinfunction "C_C") (pintype "passive"))
      (node (ref "D319") (pin "C") (pinfunction "C_C") (pintype "passive"))
      (node (ref "D327") (pin "C") (pinfunction "C_C") (pintype "passive"))
      (node (ref "D334") (pin "C") (pinfunction "C_C") (pintype "passive"))
      (node (ref "D340") (pin "C") (pinfunction "C_C") (pintype "passive"))
      (node (ref "D345") (pin "C") (pinfunction "C_C") (pintype "passive"))
      (node (ref "R3") (pin "5") (pinfunction "2_5") (pintype "passive"))
    )
    (net (code "34") (name "/Q13") (class "Default")
      (node (ref "D011") (pin "A") (pinfunction "A_A") (pintype "passive"))
      (node (ref "D012") (pin "C") (pinfunction "C_C") (pintype "passive"))
      (node (ref "D025") (pin "A") (pinfunction "A_A") (pintype "passive"))
      (node (ref "D027") (pin "C") (pinfunction "C_C") (pintype "passive"))
      (node (ref "D038") (pin "A") (pinfunction "A_A") (pintype "passive"))
      (node (ref "D041") (pin "C") (pinfunction "C_C") (pintype "passive"))
      (node (ref "D050") (pin "A") (pinfunction "A_A") (pintype "passive"))
      (node (ref "D101") (pin "A") (pinfunction "A_A") (pintype "passive"))
      (node (ref "D111") (pin "A") (pinfunction "A_A") (pintype "passive"))
      (node (ref "D120") (pin "A") (pinfunction "A_A") (pintype "passive"))
      (node (ref "D128") (pin "A") (pinfunction "A_A") (pintype "passive"))
      (node (ref "D135") (pin "A") (pinfunction "A_A") (pintype "passive"))
      (node (ref "D141") (pin "A") (pinfunction "A_A") (pintype "passive"))
      (node (ref "D146") (pin "A") (pinfunction "A_A") (pintype "passive"))
      (node (ref "D150") (pin "A") (pinfunction "A_A") (pintype "passive"))
      (node (ref "D211") (pin "C") (pinfunction "C_C") (pintype "passive"))
      (node (ref "D212") (pin "A") (pinfunction "A_A") (pintype "passive"))
      (node (ref "D225") (pin "C") (pinfunction "C_C") (pintype "passive"))
      (node (ref "D227") (pin "A") (pinfunction "A_A") (pintype "passive"))
      (node (ref "D238") (pin "C") (pinfunction "C_C") (pintype "passive"))
      (node (ref "D241") (pin "A") (pinfunction "A_A") (pintype "passive"))
      (node (ref "D250") (pin "C") (pinfunction "C_C") (pintype "passive"))
      (node (ref "D301") (pin "C") (pinfunction "C_C") (pintype "passive"))
      (node (ref "D311") (pin "C") (pinfunction "C_C") (pintype "passive"))
      (node (ref "D320") (pin "C") (pinfunction "C_C") (pintype "passive"))
      (node (ref "D328") (pin "C") (pinfunction "C_C") (pintype "passive"))
      (node (ref "D335") (pin "C") (pinfunction "C_C") (pintype "passive"))
      (node (ref "D341") (pin "C") (pinfunction "C_C") (pintype "passive"))
      (node (ref "D346") (pin "C") (pinfunction "C_C") (pintype "passive"))
      (node (ref "D350") (pin "C") (pinfunction "C_C") (pintype "passive"))
      (node (ref "R4") (pin "8") (pinfunction "2_8") (pintype "passive"))
    )
    (net (code "35") (name "/Q14") (class "Default")
      (node (ref "D012") (pin "A") (pinfunction "A_A") (pintype "passive"))
      (node (ref "D013") (pin "C") (pinfunction "C_C") (pintype "passive"))
      (node (ref "D026") (pin "A") (pinfunction "A_A") (pintype "passive"))
      (node (ref "D028") (pin "C") (pinfunction "C_C") (pintype "passive"))
      (node (ref "D039") (pin "A") (pinfunction "A_A") (pintype "passive"))
      (node (ref "D051") (pin "A") (pinfunction "A_A") (pintype "passive"))
      (node (ref "D102") (pin "A") (pinfunction "A_A") (pintype "passive"))
      (node (ref "D112") (pin "A") (pinfunction "A_A") (pintype "passive"))
      (node (ref "D121") (pin "A") (pinfunction "A_A") (pintype "passive"))
      (node (ref "D129") (pin "A") (pinfunction "A_A") (pintype "passive"))
      (node (ref "D136") (pin "A") (pinfunction "A_A") (pintype "passive"))
      (node (ref "D142") (pin "A") (pinfunction "A_A") (pintype "passive"))
      (node (ref "D147") (pin "A") (pinfunction "A_A") (pintype "passive"))
      (node (ref "D151") (pin "A") (pinfunction "A_A") (pintype "passive"))
      (node (ref "D154") (pin "A") (pinfunction "A_A") (pintype "passive"))
      (node (ref "D212") (pin "C") (pinfunction "C_C") (pintype "passive"))
      (node (ref "D213") (pin "A") (pinfunction "A_A") (pintype "passive"))
      (node (ref "D226") (pin "C") (pinfunction "C_C") (pintype "passive"))
      (node (ref "D228") (pin "A") (pinfunction "A_A") (pintype "passive"))
      (node (ref "D239") (pin "C") (pinfunction "C_C") (pintype "passive"))
      (node (ref "D251") (pin "C") (pinfunction "C_C") (pintype "passive"))
      (node (ref "D302") (pin "C") (pinfunction "C_C") (pintype "passive"))
      (node (ref "D312") (pin "C") (pinfunction "C_C") (pintype "passive"))
      (node (ref "D321") (pin "C") (pinfunction "C_C") (pintype "passive"))
      (node (ref "D329") (pin "C") (pinfunction "C_C") (pintype "passive"))
      (node (ref "D336") (pin "C") (pinfunction "C_C") (pintype "passive"))
      (node (ref "D342") (pin "C") (pinfunction "C_C") (pintype "passive"))
      (node (ref "D347") (pin "C") (pinfunction "C_C") (pintype "passive"))
      (node (ref "D351") (pin "C") (pinfunction "C_C") (pintype "passive"))
      (node (ref "D354") (pin "C") (pinfunction "C_C") (pintype "passive"))
      (node (ref "R4") (pin "7") (pinfunction "2_7") (pintype "passive"))
    )
    (net (code "36") (name "/Q15") (class "Default")
      (node (ref "D013") (pin "A") (pinfunction "A_A") (pintype "passive"))
      (node (ref "D014") (pin "C") (pinfunction "C_C") (pintype "passive"))
      (node (ref "D027") (pin "A") (pinfunction "A_A") (pintype "passive"))
      (node (ref "D040") (pin "A") (pinfunction "A_A") (pintype "passive"))
      (node (ref "D052") (pin "A") (pinfunction "A_A") (pintype "passive"))
      (node (ref "D103") (pin "A") (pinfunction "A_A") (pintype "passive"))
      (node (ref "D113") (pin "A") (pinfunction "A_A") (pintype "passive"))
      (node (ref "D122") (pin "A") (pinfunction "A_A") (pintype "passive"))
      (node (ref "D130") (pin "A") (pinfunction "A_A") (pintype "passive"))
      (node (ref "D137") (pin "A") (pinfunction "A_A") (pintype "passive"))
      (node (ref "D143") (pin "A") (pinfunction "A_A") (pintype "passive"))
      (node (ref "D148") (pin "A") (pinfunction "A_A") (pintype "passive"))
      (node (ref "D152") (pin "A") (pinfunction "A_A") (pintype "passive"))
      (node (ref "D155") (pin "A") (pinfunction "A_A") (pintype "passive"))
      (node (ref "D157") (pin "A") (pinfunction "A_A") (pintype "passive"))
      (node (ref "D213") (pin "C") (pinfunction "C_C") (pintype "passive"))
      (node (ref "D214") (pin "A") (pinfunction "A_A") (pintype "passive"))
      (node (ref "D227") (pin "C") (pinfunction "C_C") (pintype "passive"))
      (node (ref "D240") (pin "C") (pinfunction "C_C") (pintype "passive"))
      (node (ref "D252") (pin "C") (pinfunction "C_C") (pintype "passive"))
      (node (ref "D303") (pin "C") (pinfunction "C_C") (pintype "passive"))
      (node (ref "D313") (pin "C") (pinfunction "C_C") (pintype "passive"))
      (node (ref "D322") (pin "C") (pinfunction "C_C") (pintype "passive"))
      (node (ref "D330") (pin "C") (pinfunction "C_C") (pintype "passive"))
      (node (ref "D337") (pin "C") (pinfunction "C_C") (pintype "passive"))
      (node (ref "D343") (pin "C") (pinfunction "C_C") (pintype "passive"))
      (node (ref "D348") (pin "C") (pinfunction "C_C") (pintype "passive"))
      (node (ref "D352") (pin "C") (pinfunction "C_C") (pintype "passive"))
      (node (ref "D355") (pin "C") (pinfunction "C_C") (pintype "passive"))
      (node (ref "D357") (pin "C") (pinfunction "C_C") (pintype "passive"))
      (node (ref "R4") (pin "6") (pinfunction "2_6") (pintype "passive"))
    )
    (net (code "37") (name "/Q16") (class "Default")
      (node (ref "D014") (pin "A") (pinfunction "A_A") (pintype "passive"))
      (node (ref "D028") (pin "A") (pinfunction "A_A") (pintype "passive"))
      (node (ref "D041") (pin "A") (pinfunction "A_A") (pintype "passive"))
      (node (ref "D053") (pin "A") (pinfunction "A_A") (pintype "passive"))
      (node (ref "D104") (pin "A") (pinfunction "A_A") (pintype "passive"))
      (node (ref "D114") (pin "A") (pinfunction "A_A") (pintype "passive"))
      (node (ref "D123") (pin "A") (pinfunction "A_A") (pintype "passive"))
      (node (ref "D131") (pin "A") (pinfunction "A_A") (pintype "passive"))
      (node (ref "D138") (pin "A") (pinfunction "A_A") (pintype "passive"))
      (node (ref "D144") (pin "A") (pinfunction "A_A") (pintype "passive"))
      (node (ref "D149") (pin "A") (pinfunction "A_A") (pintype "passive"))
      (node (ref "D153") (pin "A") (pinfunction "A_A") (pintype "passive"))
      (node (ref "D156") (pin "A") (pinfunction "A_A") (pintype "passive"))
      (node (ref "D158") (pin "A") (pinfunction "A_A") (pintype "passive"))
      (node (ref "D159") (pin "A") (pinfunction "A_A") (pintype "passive"))
      (node (ref "D214") (pin "C") (pinfunction "C_C") (pintype "passive"))
      (node (ref "D228") (pin "C") (pinfunction "C_C") (pintype "passive"))
      (node (ref "D241") (pin "C") (pinfunction "C_C") (pintype "passive"))
      (node (ref "D253") (pin "C") (pinfunction "C_C") (pintype "passive"))
      (node (ref "D304") (pin "C") (pinfunction "C_C") (pintype "passive"))
      (node (ref "D314") (pin "C") (pinfunction "C_C") (pintype "passive"))
      (node (ref "D323") (pin "C") (pinfunction "C_C") (pintype "passive"))
      (node (ref "D331") (pin "C") (pinfunction "C_C") (pintype "passive"))
      (node (ref "D338") (pin "C") (pinfunction "C_C") (pintype "passive"))
      (node (ref "D344") (pin "C") (pinfunction "C_C") (pintype "passive"))
      (node (ref "D349") (pin "C") (pinfunction "C_C") (pintype "passive"))
      (node (ref "D353") (pin "C") (pinfunction "C_C") (pintype "passive"))
      (node (ref "D356") (pin "C") (pinfunction "C_C") (pintype "passive"))
      (node (ref "D358") (pin "C") (pinfunction "C_C") (pintype "passive"))
      (node (ref "D359") (pin "C") (pinfunction "C_C") (pintype "passive"))
      (node (ref "R4") (pin "5") (pinfunction "2_5") (pintype "passive"))
    )
    (net (code "38") (name "/RESET") (class "Default")
      (node (ref "C502") (pin "1") (pinfunction "1_1") (pintype "passive"))
      (node (ref "J003") (pin "1") (pinfunction "1_1") (pintype "passive"))
      (node (ref "R606") (pin "5") (pinfunction "2_5") (pintype "passive"))
      (node (ref "S429") (pin "P$2") (pinfunction "2_P$2") (pintype "bidirectional"))
      (node (ref "U401") (pin "29") (pinfunction "PC6(/RESET)_29") (pintype "bidirectional"))
    )
    (net (code "39") (name "/USBD+") (class "Default")
      (node (ref "J002") (pin "1") (pinfunction "1_1") (pintype "passive"))
      (node (ref "U501") (pin "15") (pinfunction "USBDP_15") (pintype "bidirectional"))
    )
    (net (code "40") (name "/USBD-") (class "Default")
      (node (ref "J002") (pin "2") (pinfunction "2_2") (pintype "passive"))
      (node (ref "U501") (pin "16") (pinfunction "USBDM_16") (pintype "bidirectional"))
    )
    (net (code "41") (name "/USB_TX") (class "Default")
      (node (ref "SJ1") (pin "3") (pinfunction "3_3") (pintype "passive"))
      (node (ref "U501") (pin "1") (pinfunction "TXD_1") (pintype "output"))
      (node (ref "U602") (pin "1") (pinfunction "I1_1") (pintype "bidirectional"))
    )
    (net (code "42") (name "/XTAL1") (class "Default")
      (node (ref "C407") (pin "2") (pinfunction "2_2") (pintype "passive"))
      (node (ref "U401") (pin "7") (pinfunction "PB6(XTAL1/TOSC1)_7") (pintype "bidirectional"))
      (node (ref "Y401") (pin "1") (pinfunction "1_1") (pintype "passive"))
    )
    (net (code "43") (name "/XTAL2") (class "Default")
      (node (ref "C408") (pin "2") (pinfunction "2_2") (pintype "passive"))
      (node (ref "U401") (pin "8") (pinfunction "PB7(XTAL2/TOSC2)_8") (pintype "bidirectional"))
      (node (ref "Y401") (pin "3") (pinfunction "2_3") (pintype "passive"))
    )
    (net (code "44") (name "GND") (class "Default")
      (node (ref "C010") (pin "2") (pinfunction "2_2") (pintype "passive"))
      (node (ref "C407") (pin "1") (pinfunction "1_1") (pintype "passive"))
      (node (ref "C408") (pin "1") (pinfunction "1_1") (pintype "passive"))
      (node (ref "C418") (pin "1") (pinfunction "1_1") (pintype "passive"))
      (node (ref "C420") (pin "2") (pinfunction "2_2") (pintype "passive"))
      (node (ref "J002") (pin "4") (pinfunction "4_4") (pintype "passive"))
      (node (ref "J003") (pin "3") (pinfunction "3_3") (pintype "passive"))
      (node (ref "J402") (pin "1") (pinfunction "GND1_1") (pintype "bidirectional"))
      (node (ref "J402") (pin "5") (pinfunction "GND2_5") (pintype "bidirectional"))
      (node (ref "J404") (pin "1") (pinfunction "GND1_1") (pintype "bidirectional"))
      (node (ref "J404") (pin "5") (pinfunction "GND2_5") (pintype "bidirectional"))
      (node (ref "S429") (pin "P$1") (pinfunction "1_P$1") (pintype "bidirectional"))
      (node (ref "S429") (pin "P$3") (pinfunction "1_P$3") (pintype "bidirectional"))
      (node (ref "U401") (pin "21") (pinfunction "GND_21") (pintype "bidirectional"))
      (node (ref "U401") (pin "3") (pinfunction "GND_3") (pintype "bidirectional"))
      (node (ref "U401") (pin "5") (pinfunction "AGND_5") (pintype "bidirectional"))
      (node (ref "U501") (pin "18") (pinfunction "GND18_18") (pintype "power_in"))
      (node (ref "U501") (pin "21") (pinfunction "GND21_21") (pintype "power_in"))
      (node (ref "U501") (pin "25") (pinfunction "AGND_25") (pintype "power_in"))
      (node (ref "U501") (pin "26") (pinfunction "TEST_26") (pintype "input"))
      (node (ref "U501") (pin "7") (pinfunction "GND7_7") (pintype "power_in"))
      (node (ref "U602") (pin "2") (pinfunction "GND_2") (pintype "bidirectional"))
      (node (ref "Y401") (pin "2") (pinfunction "1_2") (pintype "bidirectional"))
      (node (ref "Y401") (pin "4") (pinfunction "1_4") (pintype "bidirectional"))
    )
    (net (code "45") (name "Net-(D501-PadC)") (class "Default")
      (node (ref "D501") (pin "C") (pinfunction "C_C") (pintype "passive"))
      (node (ref "R501") (pin "2") (pinfunction "2_2") (pintype "passive"))
    )
    (net (code "46") (name "Net-(D502-PadC)") (class "Default")
      (node (ref "D502") (pin "C") (pinfunction "C_C") (pintype "passive"))
      (node (ref "R502") (pin "2") (pinfunction "2_2") (pintype "passive"))
    )
    (net (code "47") (name "Net-(U401-AREF)") (class "Default")
      (node (ref "C420") (pin "1") (pinfunction "1_1") (pintype "passive"))
      (node (ref "U401") (pin "20") (pinfunction "AREF_20") (pintype "bidirectional"))
    )
    (net (code "48") (name "Net-(U501-DTR)") (class "Default")
      (node (ref "C502") (pin "2") (pinfunction "2_2") (pintype "passive"))
      (node (ref "U501") (pin "2") (pinfunction "DTR_2") (pintype "output"))
    )
    (net (code "49") (name "Net-(U501-RXLED)") (class "Default")
      (node (ref "R502") (pin "1") (pinfunction "1_1") (pintype "passive"))
      (node (ref "U501") (pin "22") (pinfunction "RXLED_22") (pintype "input"))
    )
    (net (code "50") (name "Net-(U501-TXLED)") (class "Default")
      (node (ref "R501") (pin "1") (pinfunction "1_1") (pintype "passive"))
      (node (ref "U501") (pin "23") (pinfunction "TXLED_23") (pintype "input"))
    )
    (net (code "51") (name "VCC") (class "Default")
      (node (ref "C010") (pin "1") (pinfunction "1_1") (pintype "passive"))
      (node (ref "C418") (pin "2") (pinfunction "2_2") (pintype "passive"))
      (node (ref "D501") (pin "A") (pinfunction "A_A") (pintype "passive"))
      (node (ref "D502") (pin "A") (pinfunction "A_A") (pintype "passive"))
      (node (ref "J002") (pin "3") (pinfunction "3_3") (pintype "passive"))
      (node (ref "J003") (pin "2") (pinfunction "2_2") (pintype "passive"))
      (node (ref "J402") (pin "2") (pinfunction "VCC_2") (pintype "bidirectional"))
      (node (ref "J404") (pin "2") (pinfunction "VCC_2") (pintype "bidirectional"))
      (node (ref "R606") (pin "1") (pinfunction "1_1") (pintype "passive"))
      (node (ref "R606") (pin "4") (pinfunction "1_4") (pintype "passive"))
      (node (ref "U401") (pin "18") (pinfunction "AVCC_18") (pintype "bidirectional"))
      (node (ref "U401") (pin "4") (pinfunction "VCC_4") (pintype "bidirectional"))
      (node (ref "U401") (pin "6") (pinfunction "VCC_6") (pintype "bidirectional"))
      (node (ref "U501") (pin "20") (pinfunction "VCC_20") (pintype "power_in"))
      (node (ref "U501") (pin "4") (pinfunction "VCCIO_4") (pintype "power_in"))
      (node (ref "U602") (pin "5") (pinfunction "VCC_5") (pintype "bidirectional"))
    )
    (net (code "52") (name "unconnected-(U401-ADC6-Pad19)") (class "Default")
      (node (ref "U401") (pin "19") (pinfunction "ADC6_19") (pintype "bidirectional"))
    )
    (net (code "53") (name "unconnected-(U401-ADC7-Pad22)") (class "Default")
      (node (ref "U401") (pin "22") (pinfunction "ADC7_22") (pintype "bidirectional"))
    )
    (net (code "54") (name "unconnected-(U501-3V3OUT-Pad17)") (class "Default")
      (node (ref "U501") (pin "17") (pinfunction "3V3OUT_17") (pintype "output"))
    )
    (net (code "55") (name "unconnected-(U501-CTS-Pad11)") (class "Default")
      (node (ref "U501") (pin "11") (pinfunction "CTS_11") (pintype "input"))
    )
    (net (code "56") (name "unconnected-(U501-DCD-Pad10)") (class "Default")
      (node (ref "U501") (pin "10") (pinfunction "DCD_10") (pintype "input"))
    )
    (net (code "57") (name "unconnected-(U501-DSR-Pad9)") (class "Default")
      (node (ref "U501") (pin "9") (pinfunction "DSR_9") (pintype "input"))
    )
    (net (code "58") (name "unconnected-(U501-OSCI-Pad27)") (class "Default")
      (node (ref "U501") (pin "27") (pinfunction "OSCI_27") (pintype "input"))
    )
    (net (code "59") (name "unconnected-(U501-OSCO-Pad28)") (class "Default")
      (node (ref "U501") (pin "28") (pinfunction "OSCO_28") (pintype "output"))
    )
    (net (code "60") (name "unconnected-(U501-PWREN-Pad14)") (class "Default")
      (node (ref "U501") (pin "14") (pinfunction "PWREN_14") (pintype "input"))
    )
    (net (code "61") (name "unconnected-(U501-RESET-Pad19)") (class "Default")
      (node (ref "U501") (pin "19") (pinfunction "RESET_19") (pintype "input"))
    )
    (net (code "62") (name "unconnected-(U501-RI-Pad6)") (class "Default")
      (node (ref "U501") (pin "6") (pinfunction "RI_6") (pintype "input"))
    )
    (net (code "63") (name "unconnected-(U501-RTS-Pad3)") (class "Default")
      (node (ref "U501") (pin "3") (pinfunction "RTS_3") (pintype "output"))
    )
    (net (code "64") (name "unconnected-(U501-SLEEP-Pad12)") (class "Default")
      (node (ref "U501") (pin "12") (pinfunction "SLEEP_12") (pintype "input"))
    )
    (net (code "65") (name "unconnected-(U501-TXDEN-Pad13)") (class "Default")
      (node (ref "U501") (pin "13") (pinfunction "TXDEN_13") (pintype "input"))
    )
  )
)
